# yy_led_display.net
KiCad netlist of a schematic drawn in Altium Designer
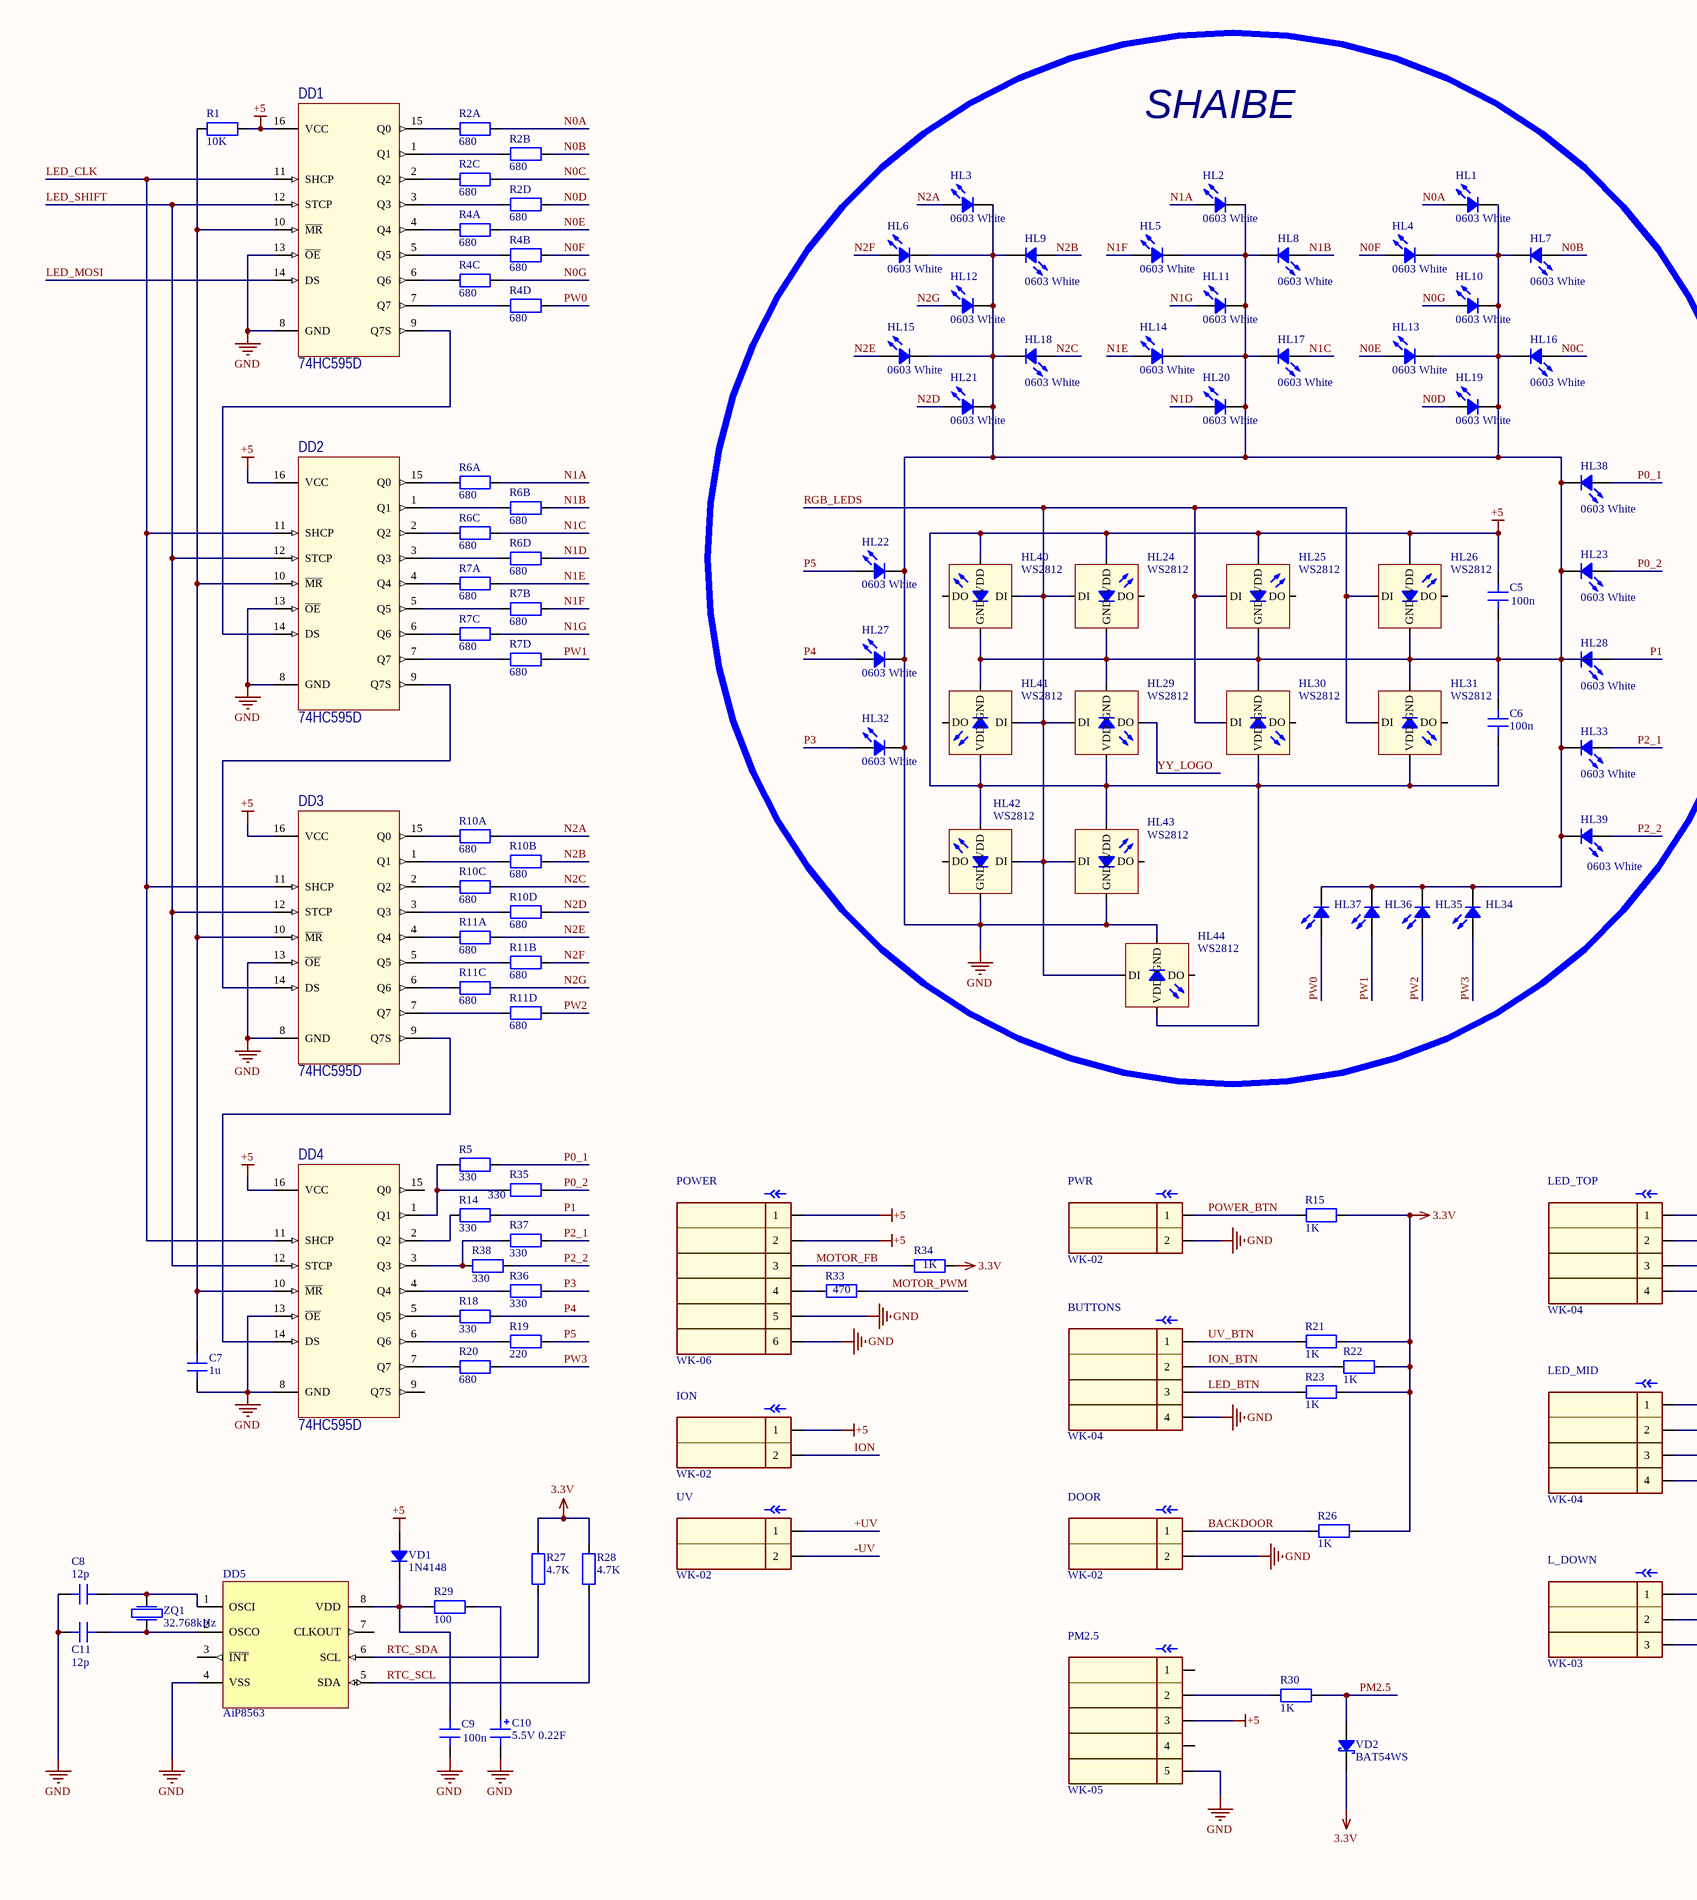
[diagram p0: yy_led_display.SchDoc, left]
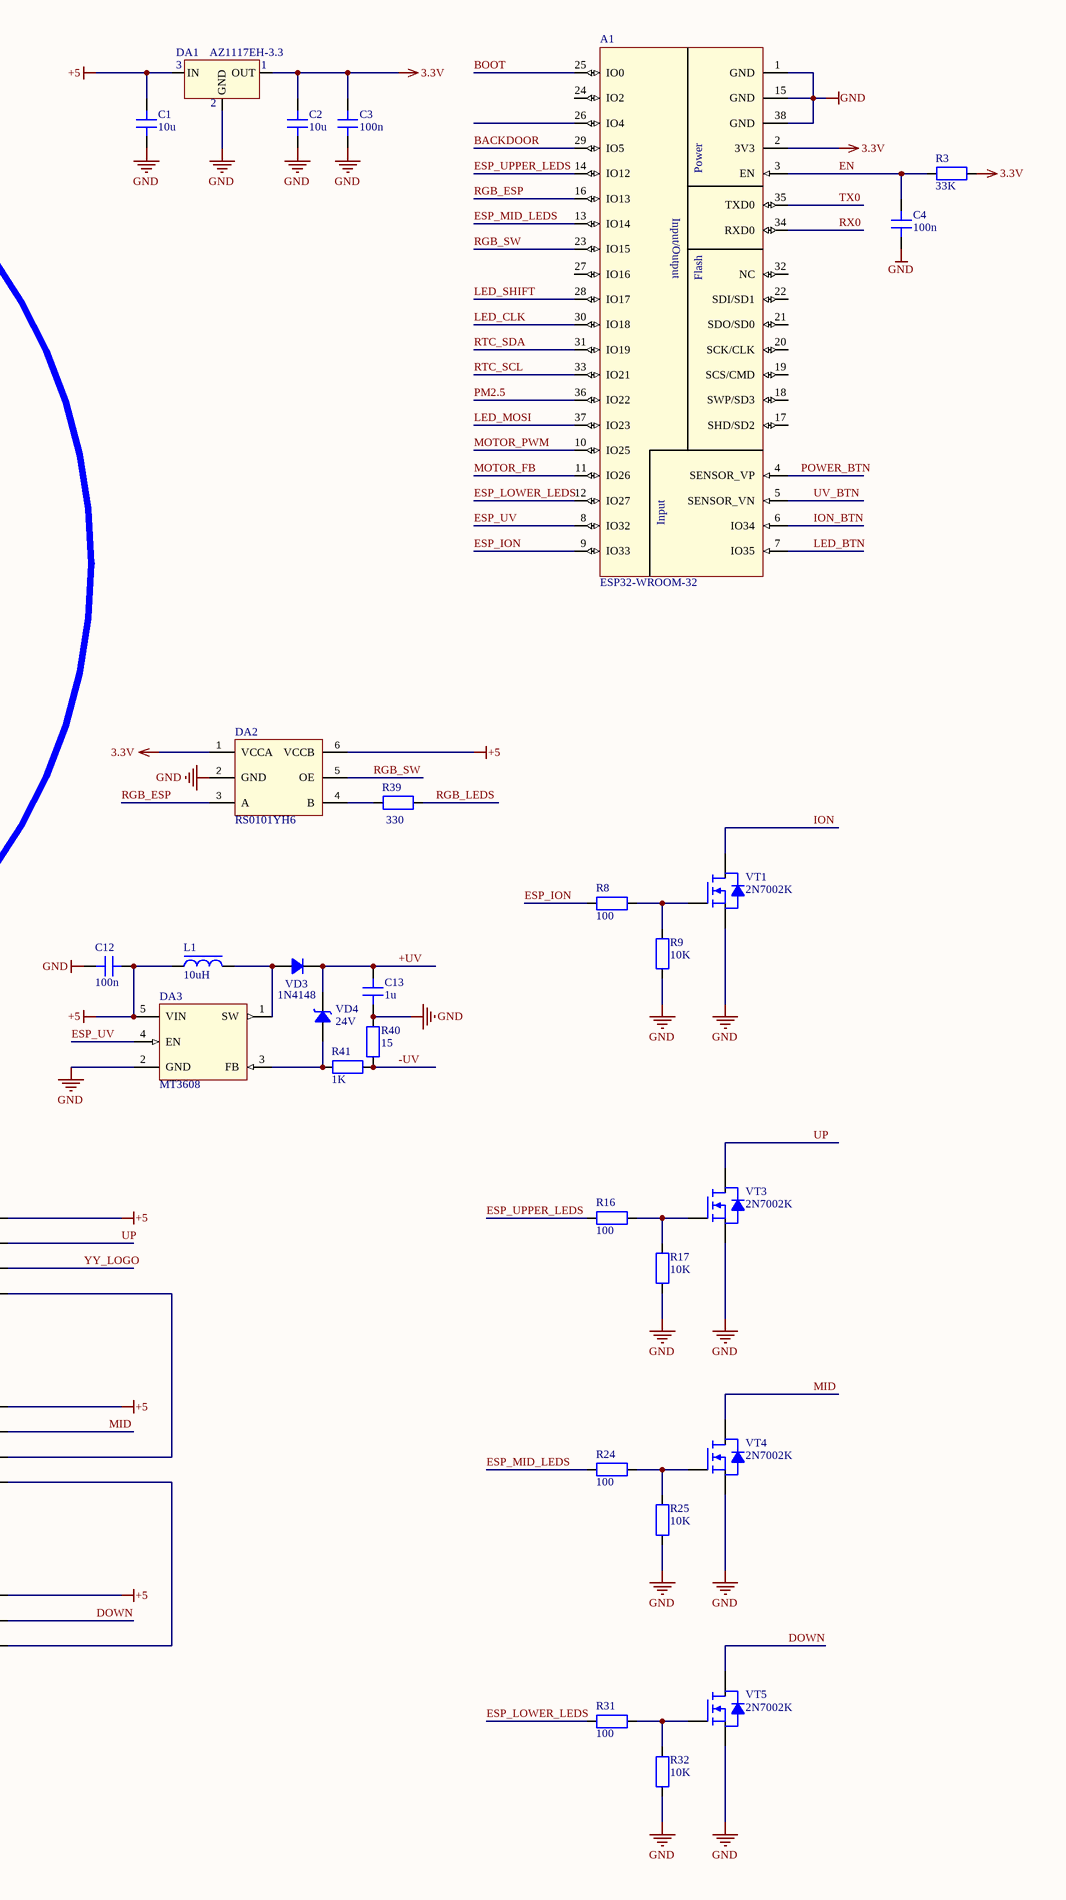
[diagram p1: yy_led_display.SchDoc, right]

(export (version "E")
  (design (tool "Eeschema 10.0.6"))
  (components
    (comp (ref "A1")
      (value "ESP32-WROOM-32")
      (footprint "ESP-WROOM-32")
      (fields (field (name "MANUFACTURER") "Espressif Systems"))
      (libsource (lib "IZTT_Library") (part "ESP32-WROOM-32"))
    )
    (comp (ref "BUTTONS")
      (value "WK-04")
      (footprint "WK-04")
      (description "Through-hole type shrouded header, XH Series, 2.5mm")
      (libsource (lib "IZTT_Library") (part "MALE_4PIN"))
    )
    (comp (ref "C1")
      (value "10u")
      (footprint "C0805")
      (description "Cap Ceramic, 0805, ±10%, 50V, X7R (X5R), -55 +125C (-55 +85C)")
      (libsource (lib "IZTT_Library") (part "Capacitor"))
    )
    (comp (ref "C2")
      (value "10u")
      (footprint "C0805")
      (description "Cap Ceramic, 0805, ±10%, 50V, X7R (X5R), -55 +125C (-55 +85C)")
      (libsource (lib "IZTT_Library") (part "Capacitor"))
    )
    (comp (ref "C3")
      (value "100n")
      (footprint "C0603")
      (description "Cap Ceramic, 0603, ±10%, 50V, X7R (X5R), -55 +125C (-55 +85C)")
      (libsource (lib "IZTT_Library") (part "Capacitor"))
    )
    (comp (ref "C4")
      (value "100n")
      (footprint "C0603")
      (description "Cap Ceramic, 0603, ±10%, 50V, X7R (X5R), -55 +125C (-55 +85C)")
      (libsource (lib "IZTT_Library") (part "Capacitor"))
    )
    (comp (ref "C5")
      (value "100n")
      (footprint "C0603")
      (description "Cap Ceramic, 0603, ±10%, 50V, X7R (X5R), -55 +125C (-55 +85C)")
      (libsource (lib "IZTT_Library") (part "Capacitor"))
    )
    (comp (ref "C6")
      (value "100n")
      (footprint "C0603")
      (description "Cap Ceramic, 0603, ±10%, 50V, X7R (X5R), -55 +125C (-55 +85C)")
      (libsource (lib "IZTT_Library") (part "Capacitor"))
    )
    (comp (ref "C7")
      (value "1u")
      (footprint "C0603")
      (description "Cap Ceramic, 0603, ±10%, 50V, X7R (X5R), -55 +125C (-55 +85C)")
      (libsource (lib "IZTT_Library") (part "Capacitor"))
    )
    (comp (ref "C8")
      (value "12p")
      (footprint "C0603")
      (description "Cap Ceramic, 0603, 5%, 50V, NPO (C0G), -55 +125C")
      (libsource (lib "IZTT_Library") (part "Capacitor"))
    )
    (comp (ref "C9")
      (value "100n")
      (footprint "C0603")
      (description "Cap Ceramic, 0603, ±10%, 50V, X7R (X5R), -55 +125C (-55 +85C)")
      (libsource (lib "IZTT_Library") (part "Capacitor"))
    )
    (comp (ref "C10")
      (value "5.5V 0.22F")
      (footprint "1207H")
      (description "Ionistor 5.5V 0.22F")
      (fields (field (name "MANUFACTURER") "WTSCAP (Wenting)"))
      (libsource (lib "IZTT_Library") (part "Capacitor_polarised"))
    )
    (comp (ref "C11")
      (value "12p")
      (footprint "C0603")
      (description "Cap Ceramic, 0603, 5%, 50V, NPO (C0G), -55 +125C")
      (libsource (lib "IZTT_Library") (part "Capacitor"))
    )
    (comp (ref "C12")
      (value "100n")
      (footprint "C0603")
      (description "Cap Ceramic, 0603, ±10%, 50V, X7R (X5R), -55 +125C (-55 +85C)")
      (libsource (lib "IZTT_Library") (part "Capacitor"))
    )
    (comp (ref "C13")
      (value "1u")
      (footprint "C0603")
      (description "Cap Ceramic, 0603, ±10%, 50V, X7R (X5R), -55 +125C (-55 +85C)")
      (libsource (lib "IZTT_Library") (part "Capacitor"))
    )
    (comp (ref "DA1")
      (value "AZ1117EH-3.3")
      (footprint "SOT-223")
      (description "IC, Vreg, LDO, For Low ESR MLCC Cout, SOT223")
      (libsource (lib "IZTT_Library") (part "LDO_1117"))
    )
    (comp (ref "DA2")
      (value "RS0101YH6")
      (footprint "SOT-23-6")
      (description "Level Translators, Shifters RoHS")
      (fields (field (name "MANUFACTURER") "Jiangsu RUNIC Tech"))
      (libsource (lib "IZTT_Library") (part "RS0101YH6"))
    )
    (comp (ref "DA3")
      (value "MT3608")
      (footprint "SOT-23-6")
      (description "High Efficiency 1.2MHz 2A Step Up Converter")
      (fields (field (name "MANUFACTURER") "XI'AN Aerosemi Tech"))
      (libsource (lib "IZTT_Library") (part "MT3608"))
    )
    (comp (ref "DD1")
      (value "74HC595D")
      (footprint "SO-16")
      (description "Shift Register Serial to parallel, serial SOIC-16_150mil")
      (fields (field (name "MANUFACTURER") "Shenzhen Fuman Elec"))
      (libsource (lib "IZTT_Library") (part "74HC595D"))
    )
    (comp (ref "DD2")
      (value "74HC595D")
      (footprint "SO-16")
      (description "Shift Register Serial to parallel, serial SOIC-16_150mil")
      (fields (field (name "MANUFACTURER") "Shenzhen Fuman Elec"))
      (libsource (lib "IZTT_Library") (part "74HC595D"))
    )
    (comp (ref "DD3")
      (value "74HC595D")
      (footprint "SO-16")
      (description "Shift Register Serial to parallel, serial SOIC-16_150mil")
      (fields (field (name "MANUFACTURER") "Shenzhen Fuman Elec"))
      (libsource (lib "IZTT_Library") (part "74HC595D"))
    )
    (comp (ref "DD4")
      (value "74HC595D")
      (footprint "SO-16")
      (description "Shift Register Serial to parallel, serial SOIC-16_150mil")
      (fields (field (name "MANUFACTURER") "Shenzhen Fuman Elec"))
      (libsource (lib "IZTT_Library") (part "74HC595D"))
    )
    (comp (ref "DD5")
      (value "AiP8563")
      (footprint "SO-8")
      (description "SOP-8 Real-time Clocks RoHS")
      (fields (field (name "MANUFACTURER") "Wuxi I-core Elec"))
      (libsource (lib "IZTT_Library") (part "AiP8563"))
    )
    (comp (ref "DOOR")
      (value "WK-02")
      (footprint "WK-02")
      (description "Through-hole type shrouded header, XH Series, 2.5mm")
      (libsource (lib "IZTT_Library") (part "MALE_2PIN"))
    )
    (comp (ref "HL1")
      (value "0603 White")
      (footprint "LED0603Y")
      (description "LED, SMD 0603, 20mA, White 6000K~7000K")
      (fields (field (name "MANUFACTURER") "HONGLITRONIC(Hongli Zhihui (HONGLITRONIC))"))
      (libsource (lib "IZTT_Library") (part "LED"))
    )
    (comp (ref "HL2")
      (value "0603 White")
      (footprint "LED0603Y")
      (description "LED, SMD 0603, 20mA, White 6000K~7000K")
      (fields (field (name "MANUFACTURER") "HONGLITRONIC(Hongli Zhihui (HONGLITRONIC))"))
      (libsource (lib "IZTT_Library") (part "LED"))
    )
    (comp (ref "HL3")
      (value "0603 White")
      (footprint "LED0603Y")
      (description "LED, SMD 0603, 20mA, White 6000K~7000K")
      (fields (field (name "MANUFACTURER") "HONGLITRONIC(Hongli Zhihui (HONGLITRONIC))"))
      (libsource (lib "IZTT_Library") (part "LED"))
    )
    (comp (ref "HL4")
      (value "0603 White")
      (footprint "LED0603Y")
      (description "LED, SMD 0603, 20mA, White 6000K~7000K")
      (fields (field (name "MANUFACTURER") "HONGLITRONIC(Hongli Zhihui (HONGLITRONIC))"))
      (libsource (lib "IZTT_Library") (part "LED"))
    )
    (comp (ref "HL5")
      (value "0603 White")
      (footprint "LED0603Y")
      (description "LED, SMD 0603, 20mA, White 6000K~7000K")
      (fields (field (name "MANUFACTURER") "HONGLITRONIC(Hongli Zhihui (HONGLITRONIC))"))
      (libsource (lib "IZTT_Library") (part "LED"))
    )
    (comp (ref "HL6")
      (value "0603 White")
      (footprint "LED0603Y")
      (description "LED, SMD 0603, 20mA, White 6000K~7000K")
      (fields (field (name "MANUFACTURER") "HONGLITRONIC(Hongli Zhihui (HONGLITRONIC))"))
      (libsource (lib "IZTT_Library") (part "LED"))
    )
    (comp (ref "HL7")
      (value "0603 White")
      (footprint "LED0603Y")
      (description "LED, SMD 0603, 20mA, White 6000K~7000K")
      (fields (field (name "MANUFACTURER") "HONGLITRONIC(Hongli Zhihui (HONGLITRONIC))"))
      (libsource (lib "IZTT_Library") (part "LED"))
    )
    (comp (ref "HL8")
      (value "0603 White")
      (footprint "LED0603Y")
      (description "LED, SMD 0603, 20mA, White 6000K~7000K")
      (fields (field (name "MANUFACTURER") "HONGLITRONIC(Hongli Zhihui (HONGLITRONIC))"))
      (libsource (lib "IZTT_Library") (part "LED"))
    )
    (comp (ref "HL9")
      (value "0603 White")
      (footprint "LED0603Y")
      (description "LED, SMD 0603, 20mA, White 6000K~7000K")
      (fields (field (name "MANUFACTURER") "HONGLITRONIC(Hongli Zhihui (HONGLITRONIC))"))
      (libsource (lib "IZTT_Library") (part "LED"))
    )
    (comp (ref "HL10")
      (value "0603 White")
      (footprint "LED0603Y")
      (description "LED, SMD 0603, 20mA, White 6000K~7000K")
      (fields (field (name "MANUFACTURER") "HONGLITRONIC(Hongli Zhihui (HONGLITRONIC))"))
      (libsource (lib "IZTT_Library") (part "LED"))
    )
    (comp (ref "HL11")
      (value "0603 White")
      (footprint "LED0603Y")
      (description "LED, SMD 0603, 20mA, White 6000K~7000K")
      (fields (field (name "MANUFACTURER") "HONGLITRONIC(Hongli Zhihui (HONGLITRONIC))"))
      (libsource (lib "IZTT_Library") (part "LED"))
    )
    (comp (ref "HL12")
      (value "0603 White")
      (footprint "LED0603Y")
      (description "LED, SMD 0603, 20mA, White 6000K~7000K")
      (fields (field (name "MANUFACTURER") "HONGLITRONIC(Hongli Zhihui (HONGLITRONIC))"))
      (libsource (lib "IZTT_Library") (part "LED"))
    )
    (comp (ref "HL13")
      (value "0603 White")
      (footprint "LED0603Y")
      (description "LED, SMD 0603, 20mA, White 6000K~7000K")
      (fields (field (name "MANUFACTURER") "HONGLITRONIC(Hongli Zhihui (HONGLITRONIC))"))
      (libsource (lib "IZTT_Library") (part "LED"))
    )
    (comp (ref "HL14")
      (value "0603 White")
      (footprint "LED0603Y")
      (description "LED, SMD 0603, 20mA, White 6000K~7000K")
      (fields (field (name "MANUFACTURER") "HONGLITRONIC(Hongli Zhihui (HONGLITRONIC))"))
      (libsource (lib "IZTT_Library") (part "LED"))
    )
    (comp (ref "HL15")
      (value "0603 White")
      (footprint "LED0603Y")
      (description "LED, SMD 0603, 20mA, White 6000K~7000K")
      (fields (field (name "MANUFACTURER") "HONGLITRONIC(Hongli Zhihui (HONGLITRONIC))"))
      (libsource (lib "IZTT_Library") (part "LED"))
    )
    (comp (ref "HL16")
      (value "0603 White")
      (footprint "LED0603Y")
      (description "LED, SMD 0603, 20mA, White 6000K~7000K")
      (fields (field (name "MANUFACTURER") "HONGLITRONIC(Hongli Zhihui (HONGLITRONIC))"))
      (libsource (lib "IZTT_Library") (part "LED"))
    )
    (comp (ref "HL17")
      (value "0603 White")
      (footprint "LED0603Y")
      (description "LED, SMD 0603, 20mA, White 6000K~7000K")
      (fields (field (name "MANUFACTURER") "HONGLITRONIC(Hongli Zhihui (HONGLITRONIC))"))
      (libsource (lib "IZTT_Library") (part "LED"))
    )
    (comp (ref "HL18")
      (value "0603 White")
      (footprint "LED0603Y")
      (description "LED, SMD 0603, 20mA, White 6000K~7000K")
      (fields (field (name "MANUFACTURER") "HONGLITRONIC(Hongli Zhihui (HONGLITRONIC))"))
      (libsource (lib "IZTT_Library") (part "LED"))
    )
    (comp (ref "HL19")
      (value "0603 White")
      (footprint "LED0603Y")
      (description "LED, SMD 0603, 20mA, White 6000K~7000K")
      (fields (field (name "MANUFACTURER") "HONGLITRONIC(Hongli Zhihui (HONGLITRONIC))"))
      (libsource (lib "IZTT_Library") (part "LED"))
    )
    (comp (ref "HL20")
      (value "0603 White")
      (footprint "LED0603Y")
      (description "LED, SMD 0603, 20mA, White 6000K~7000K")
      (fields (field (name "MANUFACTURER") "HONGLITRONIC(Hongli Zhihui (HONGLITRONIC))"))
      (libsource (lib "IZTT_Library") (part "LED"))
    )
    (comp (ref "HL21")
      (value "0603 White")
      (footprint "LED0603Y")
      (description "LED, SMD 0603, 20mA, White 6000K~7000K")
      (fields (field (name "MANUFACTURER") "HONGLITRONIC(Hongli Zhihui (HONGLITRONIC))"))
      (libsource (lib "IZTT_Library") (part "LED"))
    )
    (comp (ref "HL22")
      (value "0603 White")
      (footprint "LED0603Y")
      (description "LED, SMD 0603, 20mA, White 6000K~7000K")
      (fields (field (name "MANUFACTURER") "HONGLITRONIC(Hongli Zhihui (HONGLITRONIC))"))
      (libsource (lib "IZTT_Library") (part "LED"))
    )
    (comp (ref "HL23")
      (value "0603 White")
      (footprint "LED0603Y")
      (description "LED, SMD 0603, 20mA, White 6000K~7000K")
      (fields (field (name "MANUFACTURER") "HONGLITRONIC(Hongli Zhihui (HONGLITRONIC))"))
      (libsource (lib "IZTT_Library") (part "LED"))
    )
    (comp (ref "HL24")
      (value "WS2812")
      (footprint "WS2812C-2020")
      (description "Intelligent control LED, 2.0x2.0mm")
      (fields (field (name "MANUFACTURER") "Worldsemi"))
      (libsource (lib "IZTT_Library") (part "WS2812C-2020"))
    )
    (comp (ref "HL25")
      (value "WS2812")
      (footprint "WS2812C-2020")
      (description "Intelligent control LED, 2.0x2.0mm")
      (fields (field (name "MANUFACTURER") "Worldsemi"))
      (libsource (lib "IZTT_Library") (part "WS2812C-2020"))
    )
    (comp (ref "HL26")
      (value "WS2812")
      (footprint "WS2812C-2020")
      (description "Intelligent control LED, 2.0x2.0mm")
      (fields (field (name "MANUFACTURER") "Worldsemi"))
      (libsource (lib "IZTT_Library") (part "WS2812C-2020"))
    )
    (comp (ref "HL27")
      (value "0603 White")
      (footprint "LED0603Y")
      (description "LED, SMD 0603, 20mA, White 6000K~7000K")
      (fields (field (name "MANUFACTURER") "HONGLITRONIC(Hongli Zhihui (HONGLITRONIC))"))
      (libsource (lib "IZTT_Library") (part "LED"))
    )
    (comp (ref "HL28")
      (value "0603 White")
      (footprint "LED0603Y")
      (description "LED, SMD 0603, 20mA, White 6000K~7000K")
      (fields (field (name "MANUFACTURER") "HONGLITRONIC(Hongli Zhihui (HONGLITRONIC))"))
      (libsource (lib "IZTT_Library") (part "LED"))
    )
    (comp (ref "HL29")
      (value "WS2812")
      (footprint "WS2812C-2020")
      (description "Intelligent control LED, 2.0x2.0mm")
      (fields (field (name "MANUFACTURER") "Worldsemi"))
      (libsource (lib "") (part "WS2812C-2020_3"))
    )
    (comp (ref "HL30")
      (value "WS2812")
      (footprint "WS2812C-2020")
      (description "Intelligent control LED, 2.0x2.0mm")
      (fields (field (name "MANUFACTURER") "Worldsemi"))
      (libsource (lib "") (part "WS2812C-2020_3"))
    )
    (comp (ref "HL31")
      (value "WS2812")
      (footprint "WS2812C-2020")
      (description "Intelligent control LED, 2.0x2.0mm")
      (fields (field (name "MANUFACTURER") "Worldsemi"))
      (libsource (lib "") (part "WS2812C-2020_3"))
    )
    (comp (ref "HL32")
      (value "0603 White")
      (footprint "LED0603Y")
      (description "LED, SMD 0603, 20mA, White 6000K~7000K")
      (fields (field (name "MANUFACTURER") "HONGLITRONIC(Hongli Zhihui (HONGLITRONIC))"))
      (libsource (lib "IZTT_Library") (part "LED"))
    )
    (comp (ref "HL33")
      (value "0603 White")
      (footprint "LED0603Y")
      (description "LED, SMD 0603, 20mA, White 6000K~7000K")
      (fields (field (name "MANUFACTURER") "HONGLITRONIC(Hongli Zhihui (HONGLITRONIC))"))
      (libsource (lib "IZTT_Library") (part "LED"))
    )
    (comp (ref "HL34")
      (value "0603 White")
      (footprint "LED0603Y")
      (description "LED, SMD 0603, 20mA, White 6000K~7000K")
      (fields (field (name "MANUFACTURER") "HONGLITRONIC(Hongli Zhihui (HONGLITRONIC))"))
      (libsource (lib "IZTT_Library") (part "LED"))
    )
    (comp (ref "HL35")
      (value "0603 White")
      (footprint "LED0603Y")
      (description "LED, SMD 0603, 20mA, White 6000K~7000K")
      (fields (field (name "MANUFACTURER") "HONGLITRONIC(Hongli Zhihui (HONGLITRONIC))"))
      (libsource (lib "IZTT_Library") (part "LED"))
    )
    (comp (ref "HL36")
      (value "0603 White")
      (footprint "LED0603Y")
      (description "LED, SMD 0603, 20mA, White 6000K~7000K")
      (fields (field (name "MANUFACTURER") "HONGLITRONIC(Hongli Zhihui (HONGLITRONIC))"))
      (libsource (lib "IZTT_Library") (part "LED"))
    )
    (comp (ref "HL37")
      (value "0603 White")
      (footprint "LED0603Y")
      (description "LED, SMD 0603, 20mA, White 6000K~7000K")
      (fields (field (name "MANUFACTURER") "HONGLITRONIC(Hongli Zhihui (HONGLITRONIC))"))
      (libsource (lib "IZTT_Library") (part "LED"))
    )
    (comp (ref "HL38")
      (value "0603 White")
      (footprint "LED0603Y")
      (description "LED, SMD 0603, 20mA, White 6000K~7000K")
      (fields (field (name "MANUFACTURER") "HONGLITRONIC(Hongli Zhihui (HONGLITRONIC))"))
      (libsource (lib "IZTT_Library") (part "LED"))
    )
    (comp (ref "HL39")
      (value "0603 White")
      (footprint "LED0603Y")
      (description "LED, SMD 0603, 20mA, White 6000K~7000K")
      (fields (field (name "MANUFACTURER") "HONGLITRONIC(Hongli Zhihui (HONGLITRONIC))"))
      (libsource (lib "IZTT_Library") (part "LED"))
    )
    (comp (ref "HL40")
      (value "WS2812")
      (footprint "WS2812C-2020")
      (description "Intelligent control LED, 2.0x2.0mm")
      (fields (field (name "MANUFACTURER") "Worldsemi"))
      (libsource (lib "") (part "WS2812C-2020_1"))
    )
    (comp (ref "HL41")
      (value "WS2812")
      (footprint "WS2812C-2020")
      (description "Intelligent control LED, 2.0x2.0mm")
      (fields (field (name "MANUFACTURER") "Worldsemi"))
      (libsource (lib "") (part "WS2812C-2020_2"))
    )
    (comp (ref "HL42")
      (value "WS2812")
      (footprint "WS2812C-2020")
      (description "Intelligent control LED, 2.0x2.0mm")
      (fields (field (name "MANUFACTURER") "Worldsemi"))
      (libsource (lib "") (part "WS2812C-2020_1"))
    )
    (comp (ref "HL43")
      (value "WS2812")
      (footprint "WS2812C-2020")
      (description "Intelligent control LED, 2.0x2.0mm")
      (fields (field (name "MANUFACTURER") "Worldsemi"))
      (libsource (lib "IZTT_Library") (part "WS2812C-2020"))
    )
    (comp (ref "HL44")
      (value "WS2812")
      (footprint "WS2812C-2020")
      (description "Intelligent control LED, 2.0x2.0mm")
      (fields (field (name "MANUFACTURER") "Worldsemi"))
      (libsource (lib "") (part "WS2812C-2020_3"))
    )
    (comp (ref "ION")
      (value "WK-02")
      (footprint "WK-02")
      (description "Through-hole type shrouded header, XH Series, 2.5mm")
      (libsource (lib "IZTT_Library") (part "MALE_2PIN"))
    )
    (comp (ref "L1")
      (value "10uH")
      (footprint "SCD0302_OR_L1206")
      (description "SMD Power Inductors, 10uH ±20% 350mA 350mΩ SMD,3.5x3x2.1mm")
      (fields (field (name "MANUFACTURER") "Sunltech Tech"))
      (libsource (lib "IZTT_Library") (part "Drossel"))
    )
    (comp (ref "LED_MID")
      (value "WK-04")
      (footprint "WK-04")
      (description "Through-hole type shrouded header, XH Series, 2.5mm")
      (libsource (lib "IZTT_Library") (part "MALE_4PIN"))
    )
    (comp (ref "LED_TOP")
      (value "WK-04")
      (footprint "WK-04")
      (description "Through-hole type shrouded header, XH Series, 2.5mm")
      (libsource (lib "IZTT_Library") (part "MALE_4PIN"))
    )
    (comp (ref "L_DOWN")
      (value "WK-03")
      (footprint "WK-03")
      (description "Through-hole type shrouded header, XH Series, 2.5mm")
      (libsource (lib "IZTT_Library") (part "MALE_3PIN"))
    )
    (comp (ref "PM2.5")
      (value "WK-05")
      (footprint "WK-05")
      (description "Through-hole type shrouded header, XH Series, 2.5mm")
      (libsource (lib "IZTT_Library") (part "MALE_5PIN"))
    )
    (comp (ref "POWER")
      (value "WK-06")
      (footprint "WK-06")
      (description "Through-hole type shrouded header, XH Series, 2.5mm")
      (libsource (lib "IZTT_Library") (part "MALE_6PIN"))
    )
    (comp (ref "PWR")
      (value "WK-02")
      (footprint "WK-02")
      (description "Through-hole type shrouded header, XH Series, 2.5mm")
      (libsource (lib "IZTT_Library") (part "MALE_2PIN"))
    )
    (comp (ref "R1")
      (value "10K")
      (footprint "R0603")
      (description "Res, 0603, 1%, 1/10W")
      (fields (field (name "MANUFACTURER") "FH(Guangdong Fenghua Advanced Tech)"))
      (libsource (lib "IZTT_Library") (part "Resistor"))
    )
    (comp (ref "R2")
      (value "680")
      (footprint "RESA_4x0402")
      (description "680 ±5% 4 1/16W ±200ppm/℃ 0402_x4 Resistor Networks & Arrays RoHS")
      (fields (field (name "MANUFACTURER") "RALEC"))
      (libsource (lib "IZTT_Library") (part "Resistor_array_4"))
    )
    (comp (ref "R3")
      (value "33K")
      (footprint "R0603")
      (description "Res, 0603, 1%, 1/10W")
      (fields (field (name "MANUFACTURER") "UNI-ROYAL(Uniroyal Elec)"))
      (libsource (lib "IZTT_Library") (part "Resistor"))
    )
    (comp (ref "R4")
      (value "680")
      (footprint "RESA_4x0402")
      (description "680 ±5% 4 1/16W ±200ppm/℃ 0402_x4 Resistor Networks & Arrays RoHS")
      (fields (field (name "MANUFACTURER") "RALEC"))
      (libsource (lib "IZTT_Library") (part "Resistor_array_4"))
    )
    (comp (ref "R5")
      (value "330")
      (footprint "R0603")
      (description "Res, 0603, 1%, 1/10W")
      (fields (field (name "MANUFACTURER") "Walsin Tech Corp"))
      (libsource (lib "IZTT_Library") (part "Resistor"))
    )
    (comp (ref "R6")
      (value "680")
      (footprint "RESA_4x0402")
      (description "680 ±5% 4 1/16W ±200ppm/℃ 0402_x4 Resistor Networks & Arrays RoHS")
      (fields (field (name "MANUFACTURER") "RALEC"))
      (libsource (lib "IZTT_Library") (part "Resistor_array_4"))
    )
    (comp (ref "R7")
      (value "680")
      (footprint "RESA_4x0402")
      (description "680 ±5% 4 1/16W ±200ppm/℃ 0402_x4 Resistor Networks & Arrays RoHS")
      (fields (field (name "MANUFACTURER") "RALEC"))
      (libsource (lib "IZTT_Library") (part "Resistor_array_4"))
    )
    (comp (ref "R8")
      (value "100")
      (footprint "R0603")
      (description "Res, 0603, 1%, 1/10W")
      (fields (field (name "MANUFACTURER") "UNI-ROYAL(Uniroyal Elec)"))
      (libsource (lib "IZTT_Library") (part "Resistor"))
    )
    (comp (ref "R9")
      (value "10K")
      (footprint "R0603")
      (description "Res, 0603, 1%, 1/10W")
      (fields (field (name "MANUFACTURER") "FH(Guangdong Fenghua Advanced Tech)"))
      (libsource (lib "IZTT_Library") (part "Resistor"))
    )
    (comp (ref "R10")
      (value "680")
      (footprint "RESA_4x0402")
      (description "680 ±5% 4 1/16W ±200ppm/℃ 0402_x4 Resistor Networks & Arrays RoHS")
      (fields (field (name "MANUFACTURER") "RALEC"))
      (libsource (lib "IZTT_Library") (part "Resistor_array_4"))
    )
    (comp (ref "R11")
      (value "680")
      (footprint "RESA_4x0402")
      (description "680 ±5% 4 1/16W ±200ppm/℃ 0402_x4 Resistor Networks & Arrays RoHS")
      (fields (field (name "MANUFACTURER") "RALEC"))
      (libsource (lib "IZTT_Library") (part "Resistor_array_4"))
    )
    (comp (ref "R14")
      (value "330")
      (footprint "R0603")
      (description "Res, 0603, 1%, 1/10W")
      (fields (field (name "MANUFACTURER") "Walsin Tech Corp"))
      (libsource (lib "IZTT_Library") (part "Resistor"))
    )
    (comp (ref "R15")
      (value "1K")
      (footprint "R0603")
      (description "Res, 0603, 1%, 1/10W")
      (fields (field (name "MANUFACTURER") "FH(Guangdong Fenghua Advanced Tech)"))
      (libsource (lib "IZTT_Library") (part "Resistor"))
    )
    (comp (ref "R16")
      (value "100")
      (footprint "R0603")
      (description "Res, 0603, 1%, 1/10W")
      (fields (field (name "MANUFACTURER") "UNI-ROYAL(Uniroyal Elec)"))
      (libsource (lib "IZTT_Library") (part "Resistor"))
    )
    (comp (ref "R17")
      (value "10K")
      (footprint "R0603")
      (description "Res, 0603, 1%, 1/10W")
      (fields (field (name "MANUFACTURER") "FH(Guangdong Fenghua Advanced Tech)"))
      (libsource (lib "IZTT_Library") (part "Resistor"))
    )
    (comp (ref "R18")
      (value "330")
      (footprint "R0603")
      (description "Res, 0603, 1%, 1/10W")
      (fields (field (name "MANUFACTURER") "Walsin Tech Corp"))
      (libsource (lib "IZTT_Library") (part "Resistor"))
    )
    (comp (ref "R19")
      (value "220")
      (footprint "R0603")
      (description "Res, 0603, 1%, 1/10W")
      (fields (field (name "MANUFACTURER") "UNI-ROYAL(Uniroyal Elec)"))
      (libsource (lib "IZTT_Library") (part "Resistor"))
    )
    (comp (ref "R20")
      (value "680")
      (footprint "R0603")
      (description "Res, 0603, 1%, 1/10W")
      (fields (field (name "MANUFACTURER") "UNI-ROYAL(Uniroyal Elec)"))
      (libsource (lib "IZTT_Library") (part "Resistor"))
    )
    (comp (ref "R21")
      (value "1K")
      (footprint "R0603")
      (description "Res, 0603, 1%, 1/10W")
      (fields (field (name "MANUFACTURER") "FH(Guangdong Fenghua Advanced Tech)"))
      (libsource (lib "IZTT_Library") (part "Resistor"))
    )
    (comp (ref "R22")
      (value "1K")
      (footprint "R0603")
      (description "Res, 0603, 1%, 1/10W")
      (fields (field (name "MANUFACTURER") "FH(Guangdong Fenghua Advanced Tech)"))
      (libsource (lib "IZTT_Library") (part "Resistor"))
    )
    (comp (ref "R23")
      (value "1K")
      (footprint "R0603")
      (description "Res, 0603, 1%, 1/10W")
      (fields (field (name "MANUFACTURER") "FH(Guangdong Fenghua Advanced Tech)"))
      (libsource (lib "IZTT_Library") (part "Resistor"))
    )
    (comp (ref "R24")
      (value "100")
      (footprint "R0603")
      (description "Res, 0603, 1%, 1/10W")
      (fields (field (name "MANUFACTURER") "UNI-ROYAL(Uniroyal Elec)"))
      (libsource (lib "IZTT_Library") (part "Resistor"))
    )
    (comp (ref "R25")
      (value "10K")
      (footprint "R0603")
      (description "Res, 0603, 1%, 1/10W")
      (fields (field (name "MANUFACTURER") "FH(Guangdong Fenghua Advanced Tech)"))
      (libsource (lib "IZTT_Library") (part "Resistor"))
    )
    (comp (ref "R26")
      (value "1K")
      (footprint "R0603")
      (description "Res, 0603, 1%, 1/10W")
      (fields (field (name "MANUFACTURER") "FH(Guangdong Fenghua Advanced Tech)"))
      (libsource (lib "IZTT_Library") (part "Resistor"))
    )
    (comp (ref "R27")
      (value "4.7K")
      (footprint "R0603")
      (description "Res, 0603, 1%, 1/10W")
      (fields (field (name "MANUFACTURER") "UNI-ROYAL(Uniroyal Elec)"))
      (libsource (lib "IZTT_Library") (part "Resistor"))
    )
    (comp (ref "R28")
      (value "4.7K")
      (footprint "R0603")
      (description "Res, 0603, 1%, 1/10W")
      (fields (field (name "MANUFACTURER") "UNI-ROYAL(Uniroyal Elec)"))
      (libsource (lib "IZTT_Library") (part "Resistor"))
    )
    (comp (ref "R29")
      (value "100")
      (footprint "R0603")
      (description "Res, 0603, 1%, 1/10W")
      (fields (field (name "MANUFACTURER") "UNI-ROYAL(Uniroyal Elec)"))
      (libsource (lib "IZTT_Library") (part "Resistor"))
    )
    (comp (ref "R30")
      (value "1K")
      (footprint "R0603")
      (description "Res, 0603, 1%, 1/10W")
      (fields (field (name "MANUFACTURER") "FH(Guangdong Fenghua Advanced Tech)"))
      (libsource (lib "IZTT_Library") (part "Resistor"))
    )
    (comp (ref "R31")
      (value "100")
      (footprint "R0603")
      (description "Res, 0603, 1%, 1/10W")
      (fields (field (name "MANUFACTURER") "UNI-ROYAL(Uniroyal Elec)"))
      (libsource (lib "IZTT_Library") (part "Resistor"))
    )
    (comp (ref "R32")
      (value "10K")
      (footprint "R0603")
      (description "Res, 0603, 1%, 1/10W")
      (fields (field (name "MANUFACTURER") "FH(Guangdong Fenghua Advanced Tech)"))
      (libsource (lib "IZTT_Library") (part "Resistor"))
    )
    (comp (ref "R33")
      (value "470")
      (footprint "R0603")
      (description "Res, 0603, 1%, 1/10W")
      (fields (field (name "MANUFACTURER") "FH(Guangdong Fenghua Advanced Tech)"))
      (libsource (lib "IZTT_Library") (part "Resistor"))
    )
    (comp (ref "R34")
      (value "1K")
      (footprint "R0603")
      (description "Res, 0603, 1%, 1/10W")
      (fields (field (name "MANUFACTURER") "FH(Guangdong Fenghua Advanced Tech)"))
      (libsource (lib "IZTT_Library") (part "Resistor"))
    )
    (comp (ref "R35")
      (value "330")
      (footprint "R0603")
      (description "Res, 0603, 1%, 1/10W")
      (fields (field (name "MANUFACTURER") "Walsin Tech Corp"))
      (libsource (lib "IZTT_Library") (part "Resistor"))
    )
    (comp (ref "R36")
      (value "330")
      (footprint "R0603")
      (description "Res, 0603, 1%, 1/10W")
      (fields (field (name "MANUFACTURER") "Walsin Tech Corp"))
      (libsource (lib "IZTT_Library") (part "Resistor"))
    )
    (comp (ref "R37")
      (value "330")
      (footprint "R0603")
      (description "Res, 0603, 1%, 1/10W")
      (fields (field (name "MANUFACTURER") "Walsin Tech Corp"))
      (libsource (lib "IZTT_Library") (part "Resistor"))
    )
    (comp (ref "R38")
      (value "330")
      (footprint "R0603")
      (description "Res, 0603, 1%, 1/10W")
      (fields (field (name "MANUFACTURER") "Walsin Tech Corp"))
      (libsource (lib "IZTT_Library") (part "Resistor"))
    )
    (comp (ref "R39")
      (value "330")
      (footprint "R0603")
      (description "Res, 0603, 1%, 1/10W")
      (fields (field (name "MANUFACTURER") "Walsin Tech Corp"))
      (libsource (lib "IZTT_Library") (part "Resistor"))
    )
    (comp (ref "R40")
      (value "15")
      (footprint "R0603")
      (description "Res, 0603, 1%, 1/10W")
      (fields (field (name "MANUFACTURER") "UNI-ROYAL(Uniroyal Elec)"))
      (libsource (lib "IZTT_Library") (part "Resistor"))
    )
    (comp (ref "R41")
      (value "1K")
      (footprint "R0603")
      (description "Res, 0603, 1%, 1/10W")
      (fields (field (name "MANUFACTURER") "FH(Guangdong Fenghua Advanced Tech)"))
      (libsource (lib "IZTT_Library") (part "Resistor"))
    )
    (comp (ref "UV")
      (value "WK-02")
      (footprint "WK-02")
      (description "Through-hole type shrouded header, XH Series, 2.5mm")
      (libsource (lib "IZTT_Library") (part "MALE_2PIN"))
    )
    (comp (ref "VD1")
      (value "1N4148")
      (footprint "SOD-323_DIODE")
      (description "Small Signal Fast Switching Diode, 150mA, 75V")
      (libsource (lib "IZTT_Library") (part "Diode"))
    )
    (comp (ref "VD2")
      (value "BAT54WS")
      (footprint "SOD-323_DIODE")
      (description "30V 100mA 1V @ 100mA SOD-323 Schottky Barrier Diodes (SBD) RoHS")
      (fields (field (name "MANUFACTURER") "LGE"))
      (libsource (lib "IZTT_Library") (part "Shottky"))
    )
    (comp (ref "VD3")
      (value "1N4148")
      (footprint "SOD-323_DIODE")
      (description "Small Signal Fast Switching Diode, 150mA, 75V")
      (libsource (lib "IZTT_Library") (part "Diode"))
    )
    (comp (ref "VD4")
      (value "24V")
      (footprint "MiniMELF_Diode")
      (description "Zener Diode, 24V, 500mW, 0.1uA, LL-34")
      (fields (field (name "MANUFACTURER") "ST(Semtech)"))
      (libsource (lib "IZTT_Library") (part "Zener_TVS"))
    )
    (comp (ref "VT1")
      (value "2N7002K")
      (footprint "SOT-23-3")
      (description "HEXFET Power MOSFET N-CH")
      (libsource (lib "IZTT_Library") (part "N-MOS"))
    )
    (comp (ref "VT3")
      (value "2N7002K")
      (footprint "SOT-23-3")
      (description "HEXFET Power MOSFET N-CH")
      (libsource (lib "IZTT_Library") (part "N-MOS"))
    )
    (comp (ref "VT4")
      (value "2N7002K")
      (footprint "SOT-23-3")
      (description "HEXFET Power MOSFET N-CH")
      (libsource (lib "IZTT_Library") (part "N-MOS"))
    )
    (comp (ref "VT5")
      (value "2N7002K")
      (footprint "SOT-23-3")
      (description "HEXFET Power MOSFET N-CH")
      (libsource (lib "IZTT_Library") (part "N-MOS"))
    )
    (comp (ref "ZQ1")
      (value "32.768kHz")
      (footprint "KX-327NHT")
      (description "Quartz 32.768kHz 12.5pF 20ppm")
      (libsource (lib "IZTT_Library") (part "QUARTZ"))
    )
  )
  (nets
    (net (code "1") (name "+5") (class "Default")
      (node (ref "C1") (pin "2") (pinfunction "2_2") (pintype "passive"))
      (node (ref "C12") (pin "2") (pinfunction "2_2") (pintype "passive"))
      (node (ref "C5") (pin "2") (pinfunction "2_2") (pintype "passive"))
      (node (ref "C6") (pin "1") (pinfunction "1_1") (pintype "passive"))
      (node (ref "DA1") (pin "Z") (pinfunction "IN_Z") (pintype "passive"))
      (node (ref "DA2") (pin "6") (pinfunction "VCCB_6") (pintype "passive"))
      (node (ref "DA3") (pin "5") (pinfunction "VIN_5") (pintype "power_in"))
      (node (ref "DD1") (pin "16") (pinfunction "VCC_16") (pintype "power_in"))
      (node (ref "DD2") (pin "16") (pinfunction "VCC_16") (pintype "power_in"))
      (node (ref "DD3") (pin "16") (pinfunction "VCC_16") (pintype "power_in"))
      (node (ref "DD4") (pin "16") (pinfunction "VCC_16") (pintype "power_in"))
      (node (ref "HL24") (pin "+") (pinfunction "VDD_+") (pintype "passive"))
      (node (ref "HL25") (pin "+") (pinfunction "VDD_+") (pintype "passive"))
      (node (ref "HL26") (pin "+") (pinfunction "VDD_+") (pintype "passive"))
      (node (ref "HL29") (pin "+") (pinfunction "VDD_+") (pintype "passive"))
      (node (ref "HL30") (pin "+") (pinfunction "VDD_+") (pintype "passive"))
      (node (ref "HL31") (pin "+") (pinfunction "VDD_+") (pintype "passive"))
      (node (ref "HL40") (pin "+") (pinfunction "VDD_+") (pintype "passive"))
      (node (ref "HL41") (pin "+") (pinfunction "VDD_+") (pintype "passive"))
      (node (ref "HL42") (pin "+") (pinfunction "VDD_+") (pintype "passive"))
      (node (ref "HL43") (pin "+") (pinfunction "VDD_+") (pintype "passive"))
      (node (ref "HL44") (pin "+") (pinfunction "VDD_+") (pintype "passive"))
      (node (ref "ION") (pin "1") (pinfunction "1_1") (pintype "passive"))
      (node (ref "L1") (pin "1") (pinfunction "1_1") (pintype "passive"))
      (node (ref "LED_MID") (pin "1") (pinfunction "1_1") (pintype "passive"))
      (node (ref "LED_TOP") (pin "1") (pinfunction "1_1") (pintype "passive"))
      (node (ref "L_DOWN") (pin "1") (pinfunction "1_1") (pintype "passive"))
      (node (ref "PM2.5") (pin "3") (pinfunction "3_3") (pintype "passive"))
      (node (ref "POWER") (pin "1") (pinfunction "1_1") (pintype "passive"))
      (node (ref "POWER") (pin "2") (pinfunction "2_2") (pintype "passive"))
      (node (ref "R1") (pin "2") (pinfunction "2_2") (pintype "passive"))
      (node (ref "VD1") (pin "A") (pinfunction "A_A") (pintype "passive"))
    )
    (net (code "2") (name "/+UV") (class "Default")
      (node (ref "C13") (pin "2") (pinfunction "2_2") (pintype "passive"))
      (node (ref "UV") (pin "1") (pinfunction "1_1") (pintype "passive"))
      (node (ref "VD3") (pin "C") (pinfunction "C_C") (pintype "passive"))
      (node (ref "VD4") (pin "C") (pinfunction "C_C") (pintype "passive"))
    )
    (net (code "3") (name "/-UV") (class "Default")
      (node (ref "R40") (pin "2") (pinfunction "2_2") (pintype "passive"))
      (node (ref "R41") (pin "2") (pinfunction "2_2") (pintype "passive"))
      (node (ref "UV") (pin "2") (pinfunction "2_2") (pintype "passive"))
    )
    (net (code "4") (name "/BACKDOOR") (class "Default")
      (node (ref "A1") (pin "29") (pinfunction "IO5_29") (pintype "bidirectional"))
      (node (ref "DOOR") (pin "1") (pinfunction "1_1") (pintype "passive"))
      (node (ref "R26") (pin "1") (pinfunction "1_1") (pintype "passive"))
    )
    (net (code "5") (name "/BOOT") (class "Default")
      (node (ref "A1") (pin "25") (pinfunction "IO0_25") (pintype "bidirectional"))
    )
    (net (code "6") (name "/DOWN") (class "Default")
      (node (ref "L_DOWN") (pin "2") (pinfunction "2_2") (pintype "passive"))
      (node (ref "VT5") (pin "Y") (pinfunction "D_Y") (pintype "passive"))
    )
    (net (code "7") (name "/EN") (class "Default")
      (node (ref "A1") (pin "3") (pinfunction "EN_3") (pintype "input"))
      (node (ref "C4") (pin "2") (pinfunction "2_2") (pintype "passive"))
      (node (ref "R3") (pin "1") (pinfunction "1_1") (pintype "passive"))
    )
    (net (code "8") (name "/ESP_ION") (class "Default")
      (node (ref "A1") (pin "9") (pinfunction "IO33_9") (pintype "bidirectional"))
      (node (ref "R8") (pin "1") (pinfunction "1_1") (pintype "passive"))
    )
    (net (code "9") (name "/ESP_LOWER_LEDS") (class "Default")
      (node (ref "A1") (pin "12") (pinfunction "IO27_12") (pintype "bidirectional"))
      (node (ref "R31") (pin "1") (pinfunction "1_1") (pintype "passive"))
    )
    (net (code "10") (name "/ESP_MID_LEDS") (class "Default")
      (node (ref "A1") (pin "13") (pinfunction "IO14_13") (pintype "bidirectional"))
      (node (ref "R24") (pin "1") (pinfunction "1_1") (pintype "passive"))
    )
    (net (code "11") (name "/ESP_UPPER_LEDS") (class "Default")
      (node (ref "A1") (pin "14") (pinfunction "IO12_14") (pintype "bidirectional"))
      (node (ref "R16") (pin "1") (pinfunction "1_1") (pintype "passive"))
    )
    (net (code "12") (name "/ESP_UV") (class "Default")
      (node (ref "A1") (pin "8") (pinfunction "IO32_8") (pintype "bidirectional"))
      (node (ref "DA3") (pin "4") (pinfunction "EN_4") (pintype "input"))
    )
    (net (code "13") (name "/ION") (class "Default")
      (node (ref "ION") (pin "2") (pinfunction "2_2") (pintype "passive"))
      (node (ref "VT1") (pin "Y") (pinfunction "D_Y") (pintype "passive"))
    )
    (net (code "14") (name "/ION_BTN") (class "Default")
      (node (ref "A1") (pin "6") (pinfunction "IO34_6") (pintype "input"))
      (node (ref "BUTTONS") (pin "2") (pinfunction "2_2") (pintype "passive"))
      (node (ref "R22") (pin "1") (pinfunction "1_1") (pintype "passive"))
    )
    (net (code "15") (name "/LED_BTN") (class "Default")
      (node (ref "A1") (pin "7") (pinfunction "IO35_7") (pintype "input"))
      (node (ref "BUTTONS") (pin "3") (pinfunction "3_3") (pintype "passive"))
      (node (ref "R23") (pin "1") (pinfunction "1_1") (pintype "passive"))
    )
    (net (code "16") (name "/LED_CLK") (class "Default")
      (node (ref "A1") (pin "30") (pinfunction "IO18_30") (pintype "bidirectional"))
      (node (ref "DD1") (pin "11") (pinfunction "SHCP_11") (pintype "input"))
      (node (ref "DD2") (pin "11") (pinfunction "SHCP_11") (pintype "input"))
      (node (ref "DD3") (pin "11") (pinfunction "SHCP_11") (pintype "input"))
      (node (ref "DD4") (pin "11") (pinfunction "SHCP_11") (pintype "input"))
    )
    (net (code "17") (name "/LED_MOSI") (class "Default")
      (node (ref "A1") (pin "37") (pinfunction "IO23_37") (pintype "bidirectional"))
      (node (ref "DD1") (pin "14") (pinfunction "DS_14") (pintype "input"))
    )
    (net (code "18") (name "/LED_SHIFT") (class "Default")
      (node (ref "A1") (pin "28") (pinfunction "IO17_28") (pintype "bidirectional"))
      (node (ref "DD1") (pin "12") (pinfunction "STCP_12") (pintype "input"))
      (node (ref "DD2") (pin "12") (pinfunction "STCP_12") (pintype "input"))
      (node (ref "DD3") (pin "12") (pinfunction "STCP_12") (pintype "input"))
      (node (ref "DD4") (pin "12") (pinfunction "STCP_12") (pintype "input"))
    )
    (net (code "19") (name "/MID") (class "Default")
      (node (ref "LED_MID") (pin "2") (pinfunction "2_2") (pintype "passive"))
      (node (ref "VT4") (pin "Y") (pinfunction "D_Y") (pintype "passive"))
    )
    (net (code "20") (name "/MOTOR_FB") (class "Default")
      (node (ref "A1") (pin "11") (pinfunction "IO26_11") (pintype "bidirectional"))
      (node (ref "POWER") (pin "3") (pinfunction "3_3") (pintype "passive"))
      (node (ref "R34") (pin "1") (pinfunction "1_1") (pintype "passive"))
    )
    (net (code "21") (name "/MOTOR_PWM") (class "Default")
      (node (ref "A1") (pin "10") (pinfunction "IO25_10") (pintype "bidirectional"))
      (node (ref "R33") (pin "2") (pinfunction "2_2") (pintype "passive"))
    )
    (net (code "22") (name "/N0A") (class "Default")
      (node (ref "HL1") (pin "A") (pinfunction "A_A") (pintype "passive"))
      (node (ref "R2") (pin "A2") (pinfunction "A2_A2") (pintype "passive"))
    )
    (net (code "23") (name "/N0B") (class "Default")
      (node (ref "HL7") (pin "A") (pinfunction "A_A") (pintype "passive"))
      (node (ref "R2") (pin "B2") (pinfunction "B2_B2") (pintype "passive"))
    )
    (net (code "24") (name "/N0C") (class "Default")
      (node (ref "HL16") (pin "A") (pinfunction "A_A") (pintype "passive"))
      (node (ref "R2") (pin "C2") (pinfunction "C2_C2") (pintype "passive"))
    )
    (net (code "25") (name "/N0D") (class "Default")
      (node (ref "HL19") (pin "A") (pinfunction "A_A") (pintype "passive"))
      (node (ref "R2") (pin "D2") (pinfunction "D2_D2") (pintype "passive"))
    )
    (net (code "26") (name "/N0E") (class "Default")
      (node (ref "HL13") (pin "A") (pinfunction "A_A") (pintype "passive"))
      (node (ref "R4") (pin "A2") (pinfunction "A2_A2") (pintype "passive"))
    )
    (net (code "27") (name "/N0F") (class "Default")
      (node (ref "HL4") (pin "A") (pinfunction "A_A") (pintype "passive"))
      (node (ref "R4") (pin "B2") (pinfunction "B2_B2") (pintype "passive"))
    )
    (net (code "28") (name "/N0G") (class "Default")
      (node (ref "HL10") (pin "A") (pinfunction "A_A") (pintype "passive"))
      (node (ref "R4") (pin "C2") (pinfunction "C2_C2") (pintype "passive"))
    )
    (net (code "29") (name "/N1A") (class "Default")
      (node (ref "HL2") (pin "A") (pinfunction "A_A") (pintype "passive"))
      (node (ref "R6") (pin "A2") (pinfunction "A2_A2") (pintype "passive"))
    )
    (net (code "30") (name "/N1B") (class "Default")
      (node (ref "HL8") (pin "A") (pinfunction "A_A") (pintype "passive"))
      (node (ref "R6") (pin "B2") (pinfunction "B2_B2") (pintype "passive"))
    )
    (net (code "31") (name "/N1C") (class "Default")
      (node (ref "HL17") (pin "A") (pinfunction "A_A") (pintype "passive"))
      (node (ref "R6") (pin "C2") (pinfunction "C2_C2") (pintype "passive"))
    )
    (net (code "32") (name "/N1D") (class "Default")
      (node (ref "HL20") (pin "A") (pinfunction "A_A") (pintype "passive"))
      (node (ref "R6") (pin "D2") (pinfunction "D2_D2") (pintype "passive"))
    )
    (net (code "33") (name "/N1E") (class "Default")
      (node (ref "HL14") (pin "A") (pinfunction "A_A") (pintype "passive"))
      (node (ref "R7") (pin "A2") (pinfunction "A2_A2") (pintype "passive"))
    )
    (net (code "34") (name "/N1F") (class "Default")
      (node (ref "HL5") (pin "A") (pinfunction "A_A") (pintype "passive"))
      (node (ref "R7") (pin "B2") (pinfunction "B2_B2") (pintype "passive"))
    )
    (net (code "35") (name "/N1G") (class "Default")
      (node (ref "HL11") (pin "A") (pinfunction "A_A") (pintype "passive"))
      (node (ref "R7") (pin "C2") (pinfunction "C2_C2") (pintype "passive"))
    )
    (net (code "36") (name "/N2A") (class "Default")
      (node (ref "HL3") (pin "A") (pinfunction "A_A") (pintype "passive"))
      (node (ref "R10") (pin "A2") (pinfunction "A2_A2") (pintype "passive"))
    )
    (net (code "37") (name "/N2B") (class "Default")
      (node (ref "HL9") (pin "A") (pinfunction "A_A") (pintype "passive"))
      (node (ref "R10") (pin "B2") (pinfunction "B2_B2") (pintype "passive"))
    )
    (net (code "38") (name "/N2C") (class "Default")
      (node (ref "HL18") (pin "A") (pinfunction "A_A") (pintype "passive"))
      (node (ref "R10") (pin "C2") (pinfunction "C2_C2") (pintype "passive"))
    )
    (net (code "39") (name "/N2D") (class "Default")
      (node (ref "HL21") (pin "A") (pinfunction "A_A") (pintype "passive"))
      (node (ref "R10") (pin "D2") (pinfunction "D2_D2") (pintype "passive"))
    )
    (net (code "40") (name "/N2E") (class "Default")
      (node (ref "HL15") (pin "A") (pinfunction "A_A") (pintype "passive"))
      (node (ref "R11") (pin "A2") (pinfunction "A2_A2") (pintype "passive"))
    )
    (net (code "41") (name "/N2F") (class "Default")
      (node (ref "HL6") (pin "A") (pinfunction "A_A") (pintype "passive"))
      (node (ref "R11") (pin "B2") (pinfunction "B2_B2") (pintype "passive"))
    )
    (net (code "42") (name "/N2G") (class "Default")
      (node (ref "HL12") (pin "A") (pinfunction "A_A") (pintype "passive"))
      (node (ref "R11") (pin "C2") (pinfunction "C2_C2") (pintype "passive"))
    )
    (net (code "43") (name "/P0_1") (class "Default")
      (node (ref "HL38") (pin "A") (pinfunction "A_A") (pintype "passive"))
      (node (ref "R5") (pin "2") (pinfunction "2_2") (pintype "passive"))
    )
    (net (code "44") (name "/P0_2") (class "Default")
      (node (ref "HL23") (pin "A") (pinfunction "A_A") (pintype "passive"))
      (node (ref "R35") (pin "2") (pinfunction "2_2") (pintype "passive"))
    )
    (net (code "45") (name "/P1") (class "Default")
      (node (ref "HL28") (pin "A") (pinfunction "A_A") (pintype "passive"))
      (node (ref "R14") (pin "2") (pinfunction "2_2") (pintype "passive"))
    )
    (net (code "46") (name "/P2_1") (class "Default")
      (node (ref "HL33") (pin "A") (pinfunction "A_A") (pintype "passive"))
      (node (ref "R37") (pin "2") (pinfunction "2_2") (pintype "passive"))
    )
    (net (code "47") (name "/P2_2") (class "Default")
      (node (ref "HL39") (pin "A") (pinfunction "A_A") (pintype "passive"))
      (node (ref "R38") (pin "2") (pinfunction "2_2") (pintype "passive"))
    )
    (net (code "48") (name "/P3") (class "Default")
      (node (ref "HL32") (pin "A") (pinfunction "A_A") (pintype "passive"))
      (node (ref "R36") (pin "2") (pinfunction "2_2") (pintype "passive"))
    )
    (net (code "49") (name "/P4") (class "Default")
      (node (ref "HL27") (pin "A") (pinfunction "A_A") (pintype "passive"))
      (node (ref "R18") (pin "2") (pinfunction "2_2") (pintype "passive"))
    )
    (net (code "50") (name "/P5") (class "Default")
      (node (ref "HL22") (pin "A") (pinfunction "A_A") (pintype "passive"))
      (node (ref "R19") (pin "2") (pinfunction "2_2") (pintype "passive"))
    )
    (net (code "51") (name "/PM2.5") (class "Default")
      (node (ref "A1") (pin "36") (pinfunction "IO22_36") (pintype "bidirectional"))
      (node (ref "R30") (pin "2") (pinfunction "2_2") (pintype "passive"))
      (node (ref "VD2") (pin "A") (pinfunction "A_A") (pintype "passive"))
    )
    (net (code "52") (name "/POWER_BTN") (class "Default")
      (node (ref "A1") (pin "4") (pinfunction "SENSOR_VP_4") (pintype "input"))
      (node (ref "PWR") (pin "1") (pinfunction "1_1") (pintype "passive"))
      (node (ref "R15") (pin "1") (pinfunction "1_1") (pintype "passive"))
    )
    (net (code "53") (name "/PW0") (class "Default")
      (node (ref "HL37") (pin "A") (pinfunction "A_A") (pintype "passive"))
      (node (ref "R4") (pin "D2") (pinfunction "D2_D2") (pintype "passive"))
    )
    (net (code "54") (name "/PW1") (class "Default")
      (node (ref "HL36") (pin "A") (pinfunction "A_A") (pintype "passive"))
      (node (ref "R7") (pin "D2") (pinfunction "D2_D2") (pintype "passive"))
    )
    (net (code "55") (name "/PW2") (class "Default")
      (node (ref "HL35") (pin "A") (pinfunction "A_A") (pintype "passive"))
      (node (ref "R11") (pin "D2") (pinfunction "D2_D2") (pintype "passive"))
    )
    (net (code "56") (name "/PW3") (class "Default")
      (node (ref "HL34") (pin "A") (pinfunction "A_A") (pintype "passive"))
      (node (ref "R20") (pin "2") (pinfunction "2_2") (pintype "passive"))
    )
    (net (code "57") (name "/RGB_ESP") (class "Default")
      (node (ref "A1") (pin "16") (pinfunction "IO13_16") (pintype "bidirectional"))
      (node (ref "DA2") (pin "3") (pinfunction "A_3") (pintype "passive"))
    )
    (net (code "58") (name "/RGB_LEDS") (class "Default")
      (node (ref "HL24") (pin "I") (pinfunction "DI_I") (pintype "passive"))
      (node (ref "HL25") (pin "I") (pinfunction "DI_I") (pintype "passive"))
      (node (ref "HL26") (pin "I") (pinfunction "DI_I") (pintype "passive"))
      (node (ref "HL29") (pin "I") (pinfunction "DI_I") (pintype "passive"))
      (node (ref "HL30") (pin "I") (pinfunction "DI_I") (pintype "passive"))
      (node (ref "HL31") (pin "I") (pinfunction "DI_I") (pintype "passive"))
      (node (ref "HL40") (pin "I") (pinfunction "DI_I") (pintype "passive"))
      (node (ref "HL41") (pin "I") (pinfunction "DI_I") (pintype "passive"))
      (node (ref "HL42") (pin "I") (pinfunction "DI_I") (pintype "passive"))
      (node (ref "HL43") (pin "I") (pinfunction "DI_I") (pintype "passive"))
      (node (ref "HL44") (pin "I") (pinfunction "DI_I") (pintype "passive"))
      (node (ref "R39") (pin "2") (pinfunction "2_2") (pintype "passive"))
    )
    (net (code "59") (name "/RGB_SW") (class "Default")
      (node (ref "A1") (pin "23") (pinfunction "IO15_23") (pintype "bidirectional"))
      (node (ref "DA2") (pin "5") (pinfunction "OE_5") (pintype "passive"))
    )
    (net (code "60") (name "/RTC_SCL") (class "Default")
      (node (ref "A1") (pin "33") (pinfunction "IO21_33") (pintype "bidirectional"))
      (node (ref "DD5") (pin "5") (pinfunction "SDA_5") (pintype "bidirectional"))
      (node (ref "R28") (pin "1") (pinfunction "1_1") (pintype "passive"))
    )
    (net (code "61") (name "/RTC_SDA") (class "Default")
      (node (ref "A1") (pin "31") (pinfunction "IO19_31") (pintype "bidirectional"))
      (node (ref "DD5") (pin "6") (pinfunction "SCL_6") (pintype "input"))
      (node (ref "R27") (pin "1") (pinfunction "1_1") (pintype "passive"))
    )
    (net (code "62") (name "/RX0") (class "Default")
      (node (ref "A1") (pin "34") (pinfunction "RXD0_34") (pintype "bidirectional"))
    )
    (net (code "63") (name "/TX0") (class "Default")
      (node (ref "A1") (pin "35") (pinfunction "TXD0_35") (pintype "bidirectional"))
    )
    (net (code "64") (name "/UP") (class "Default")
      (node (ref "LED_TOP") (pin "2") (pinfunction "2_2") (pintype "passive"))
      (node (ref "VT3") (pin "Y") (pinfunction "D_Y") (pintype "passive"))
    )
    (net (code "65") (name "/UV_BTN") (class "Default")
      (node (ref "A1") (pin "5") (pinfunction "SENSOR_VN_5") (pintype "input"))
      (node (ref "BUTTONS") (pin "1") (pinfunction "1_1") (pintype "passive"))
      (node (ref "R21") (pin "1") (pinfunction "1_1") (pintype "passive"))
    )
    (net (code "66") (name "/YY_LOGO") (class "Default")
      (node (ref "HL29") (pin "O") (pinfunction "DO_O") (pintype "passive"))
      (node (ref "LED_TOP") (pin "3") (pinfunction "3_3") (pintype "passive"))
    )
    (net (code "67") (name "3.3V") (class "Default")
      (node (ref "A1") (pin "2") (pinfunction "3V3_2") (pintype "power_in"))
      (node (ref "C2") (pin "2") (pinfunction "2_2") (pintype "passive"))
      (node (ref "C3") (pin "2") (pinfunction "2_2") (pintype "passive"))
      (node (ref "DA1") (pin "Y") (pinfunction "OUT_Y") (pintype "passive"))
      (node (ref "DA2") (pin "1") (pinfunction "VCCA_1") (pintype "passive"))
      (node (ref "R15") (pin "2") (pinfunction "2_2") (pintype "passive"))
      (node (ref "R21") (pin "2") (pinfunction "2_2") (pintype "passive"))
      (node (ref "R22") (pin "2") (pinfunction "2_2") (pintype "passive"))
      (node (ref "R23") (pin "2") (pinfunction "2_2") (pintype "passive"))
      (node (ref "R26") (pin "2") (pinfunction "2_2") (pintype "passive"))
      (node (ref "R27") (pin "2") (pinfunction "2_2") (pintype "passive"))
      (node (ref "R28") (pin "2") (pinfunction "2_2") (pintype "passive"))
      (node (ref "R3") (pin "2") (pinfunction "2_2") (pintype "passive"))
      (node (ref "R34") (pin "2") (pinfunction "2_2") (pintype "passive"))
      (node (ref "VD2") (pin "C") (pinfunction "C_C") (pintype "passive"))
    )
    (net (code "68") (name "GND") (class "Default")
      (node (ref "A1") (pin "1") (pinfunction "GND_1") (pintype "power_in"))
      (node (ref "A1") (pin "15") (pinfunction "GND_15") (pintype "power_in"))
      (node (ref "A1") (pin "38") (pinfunction "GND_38") (pintype "power_in"))
      (node (ref "BUTTONS") (pin "4") (pinfunction "4_4") (pintype "passive"))
      (node (ref "C1") (pin "1") (pinfunction "1_1") (pintype "passive"))
      (node (ref "C10") (pin "-") (pinfunction "-_-") (pintype "passive"))
      (node (ref "C11") (pin "1") (pinfunction "1_1") (pintype "passive"))
      (node (ref "C12") (pin "1") (pinfunction "1_1") (pintype "passive"))
      (node (ref "C13") (pin "1") (pinfunction "1_1") (pintype "passive"))
      (node (ref "C2") (pin "1") (pinfunction "1_1") (pintype "passive"))
      (node (ref "C3") (pin "1") (pinfunction "1_1") (pintype "passive"))
      (node (ref "C4") (pin "1") (pinfunction "1_1") (pintype "passive"))
      (node (ref "C5") (pin "1") (pinfunction "1_1") (pintype "passive"))
      (node (ref "C6") (pin "2") (pinfunction "2_2") (pintype "passive"))
      (node (ref "C7") (pin "1") (pinfunction "1_1") (pintype "passive"))
      (node (ref "C8") (pin "1") (pinfunction "1_1") (pintype "passive"))
      (node (ref "C9") (pin "2") (pinfunction "2_2") (pintype "passive"))
      (node (ref "DA1") (pin "X") (pinfunction "GND_X") (pintype "passive"))
      (node (ref "DA2") (pin "2") (pinfunction "GND_2") (pintype "passive"))
      (node (ref "DA3") (pin "2") (pinfunction "GND_2") (pintype "passive"))
      (node (ref "DD1") (pin "13") (pinfunction "~{OE}_13") (pintype "input"))
      (node (ref "DD1") (pin "8") (pinfunction "GND_8") (pintype "power_in"))
      (node (ref "DD2") (pin "13") (pinfunction "~{OE}_13") (pintype "input"))
      (node (ref "DD2") (pin "8") (pinfunction "GND_8") (pintype "power_in"))
      (node (ref "DD3") (pin "13") (pinfunction "~{OE}_13") (pintype "input"))
      (node (ref "DD3") (pin "8") (pinfunction "GND_8") (pintype "power_in"))
      (node (ref "DD4") (pin "13") (pinfunction "~{OE}_13") (pintype "input"))
      (node (ref "DD4") (pin "8") (pinfunction "GND_8") (pintype "power_in"))
      (node (ref "DD5") (pin "4") (pinfunction "VSS_4") (pintype "power_in"))
      (node (ref "DOOR") (pin "2") (pinfunction "2_2") (pintype "passive"))
      (node (ref "HL1") (pin "C") (pinfunction "C_C") (pintype "passive"))
      (node (ref "HL10") (pin "C") (pinfunction "C_C") (pintype "passive"))
      (node (ref "HL11") (pin "C") (pinfunction "C_C") (pintype "passive"))
      (node (ref "HL12") (pin "C") (pinfunction "C_C") (pintype "passive"))
      (node (ref "HL13") (pin "C") (pinfunction "C_C") (pintype "passive"))
      (node (ref "HL14") (pin "C") (pinfunction "C_C") (pintype "passive"))
      (node (ref "HL15") (pin "C") (pinfunction "C_C") (pintype "passive"))
      (node (ref "HL16") (pin "C") (pinfunction "C_C") (pintype "passive"))
      (node (ref "HL17") (pin "C") (pinfunction "C_C") (pintype "passive"))
      (node (ref "HL18") (pin "C") (pinfunction "C_C") (pintype "passive"))
      (node (ref "HL19") (pin "C") (pinfunction "C_C") (pintype "passive"))
      (node (ref "HL2") (pin "C") (pinfunction "C_C") (pintype "passive"))
      (node (ref "HL20") (pin "C") (pinfunction "C_C") (pintype "passive"))
      (node (ref "HL21") (pin "C") (pinfunction "C_C") (pintype "passive"))
      (node (ref "HL22") (pin "C") (pinfunction "C_C") (pintype "passive"))
      (node (ref "HL23") (pin "C") (pinfunction "C_C") (pintype "passive"))
      (node (ref "HL24") (pin "-") (pinfunction "GND_-") (pintype "passive"))
      (node (ref "HL25") (pin "-") (pinfunction "GND_-") (pintype "passive"))
      (node (ref "HL26") (pin "-") (pinfunction "GND_-") (pintype "passive"))
      (node (ref "HL27") (pin "C") (pinfunction "C_C") (pintype "passive"))
      (node (ref "HL28") (pin "C") (pinfunction "C_C") (pintype "passive"))
      (node (ref "HL29") (pin "-") (pinfunction "GND_-") (pintype "passive"))
      (node (ref "HL3") (pin "C") (pinfunction "C_C") (pintype "passive"))
      (node (ref "HL30") (pin "-") (pinfunction "GND_-") (pintype "passive"))
      (node (ref "HL31") (pin "-") (pinfunction "GND_-") (pintype "passive"))
      (node (ref "HL32") (pin "C") (pinfunction "C_C") (pintype "passive"))
      (node (ref "HL33") (pin "C") (pinfunction "C_C") (pintype "passive"))
      (node (ref "HL34") (pin "C") (pinfunction "C_C") (pintype "passive"))
      (node (ref "HL35") (pin "C") (pinfunction "C_C") (pintype "passive"))
      (node (ref "HL36") (pin "C") (pinfunction "C_C") (pintype "passive"))
      (node (ref "HL37") (pin "C") (pinfunction "C_C") (pintype "passive"))
      (node (ref "HL38") (pin "C") (pinfunction "C_C") (pintype "passive"))
      (node (ref "HL39") (pin "C") (pinfunction "C_C") (pintype "passive"))
      (node (ref "HL4") (pin "C") (pinfunction "C_C") (pintype "passive"))
      (node (ref "HL40") (pin "-") (pinfunction "GND_-") (pintype "passive"))
      (node (ref "HL41") (pin "-") (pinfunction "GND_-") (pintype "passive"))
      (node (ref "HL42") (pin "-") (pinfunction "GND_-") (pintype "passive"))
      (node (ref "HL43") (pin "-") (pinfunction "GND_-") (pintype "passive"))
      (node (ref "HL44") (pin "-") (pinfunction "GND_-") (pintype "passive"))
      (node (ref "HL5") (pin "C") (pinfunction "C_C") (pintype "passive"))
      (node (ref "HL6") (pin "C") (pinfunction "C_C") (pintype "passive"))
      (node (ref "HL7") (pin "C") (pinfunction "C_C") (pintype "passive"))
      (node (ref "HL8") (pin "C") (pinfunction "C_C") (pintype "passive"))
      (node (ref "HL9") (pin "C") (pinfunction "C_C") (pintype "passive"))
      (node (ref "PM2.5") (pin "5") (pinfunction "5_5") (pintype "passive"))
      (node (ref "POWER") (pin "5") (pinfunction "5_5") (pintype "passive"))
      (node (ref "POWER") (pin "6") (pinfunction "6_6") (pintype "passive"))
      (node (ref "PWR") (pin "2") (pinfunction "2_2") (pintype "passive"))
      (node (ref "R17") (pin "1") (pinfunction "1_1") (pintype "passive"))
      (node (ref "R25") (pin "1") (pinfunction "1_1") (pintype "passive"))
      (node (ref "R32") (pin "1") (pinfunction "1_1") (pintype "passive"))
      (node (ref "R40") (pin "1") (pinfunction "1_1") (pintype "passive"))
      (node (ref "R9") (pin "1") (pinfunction "1_1") (pintype "passive"))
      (node (ref "VT1") (pin "Z") (pinfunction "S_Z") (pintype "passive"))
      (node (ref "VT3") (pin "Z") (pinfunction "S_Z") (pintype "passive"))
      (node (ref "VT4") (pin "Z") (pinfunction "S_Z") (pintype "passive"))
      (node (ref "VT5") (pin "Z") (pinfunction "S_Z") (pintype "passive"))
    )
    (net (code "69") (name "Net-(C10-Pad+)") (class "Default")
      (node (ref "C10") (pin "+") (pinfunction "+_+") (pintype "passive"))
      (node (ref "R29") (pin "2") (pinfunction "2_2") (pintype "passive"))
    )
    (net (code "70") (name "Net-(DA2-B)") (class "Default")
      (node (ref "DA2") (pin "4") (pinfunction "B_4") (pintype "passive"))
      (node (ref "R39") (pin "1") (pinfunction "1_1") (pintype "passive"))
    )
    (net (code "71") (name "Net-(DA3-FB)") (class "Default")
      (node (ref "DA3") (pin "3") (pinfunction "FB_3") (pintype "input"))
      (node (ref "R41") (pin "1") (pinfunction "1_1") (pintype "passive"))
      (node (ref "VD4") (pin "A") (pinfunction "A_A") (pintype "passive"))
    )
    (net (code "72") (name "Net-(DA3-SW)") (class "Default")
      (node (ref "DA3") (pin "1") (pinfunction "SW_1") (pintype "output"))
      (node (ref "L1") (pin "2") (pinfunction "2_2") (pintype "passive"))
      (node (ref "VD3") (pin "A") (pinfunction "A_A") (pintype "passive"))
    )
    (net (code "73") (name "Net-(DD1-Q0)") (class "Default")
      (node (ref "DD1") (pin "15") (pinfunction "Q0_15") (pintype "output"))
      (node (ref "R2") (pin "A1") (pinfunction "A1_A1") (pintype "passive"))
    )
    (net (code "74") (name "Net-(DD1-Q1)") (class "Default")
      (node (ref "DD1") (pin "1") (pinfunction "Q1_1") (pintype "output"))
      (node (ref "R2") (pin "B1") (pinfunction "B1_B1") (pintype "passive"))
    )
    (net (code "75") (name "Net-(DD1-Q2)") (class "Default")
      (node (ref "DD1") (pin "2") (pinfunction "Q2_2") (pintype "output"))
      (node (ref "R2") (pin "C1") (pinfunction "C1_C1") (pintype "passive"))
    )
    (net (code "76") (name "Net-(DD1-Q3)") (class "Default")
      (node (ref "DD1") (pin "3") (pinfunction "Q3_3") (pintype "output"))
      (node (ref "R2") (pin "D1") (pinfunction "D1_D1") (pintype "passive"))
    )
    (net (code "77") (name "Net-(DD1-Q4)") (class "Default")
      (node (ref "DD1") (pin "4") (pinfunction "Q4_4") (pintype "output"))
      (node (ref "R4") (pin "A1") (pinfunction "A1_A1") (pintype "passive"))
    )
    (net (code "78") (name "Net-(DD1-Q5)") (class "Default")
      (node (ref "DD1") (pin "5") (pinfunction "Q5_5") (pintype "output"))
      (node (ref "R4") (pin "B1") (pinfunction "B1_B1") (pintype "passive"))
    )
    (net (code "79") (name "Net-(DD1-Q6)") (class "Default")
      (node (ref "DD1") (pin "6") (pinfunction "Q6_6") (pintype "output"))
      (node (ref "R4") (pin "C1") (pinfunction "C1_C1") (pintype "passive"))
    )
    (net (code "80") (name "Net-(DD1-Q7)") (class "Default")
      (node (ref "DD1") (pin "7") (pinfunction "Q7_7") (pintype "output"))
      (node (ref "R4") (pin "D1") (pinfunction "D1_D1") (pintype "passive"))
    )
    (net (code "81") (name "Net-(DD1-Q7S)") (class "Default")
      (node (ref "DD1") (pin "9") (pinfunction "Q7S_9") (pintype "output"))
      (node (ref "DD2") (pin "14") (pinfunction "DS_14") (pintype "input"))
    )
    (net (code "82") (name "Net-(DD1-~{MR})") (class "Default")
      (node (ref "C7") (pin "2") (pinfunction "2_2") (pintype "passive"))
      (node (ref "DD1") (pin "10") (pinfunction "~{MR}_10") (pintype "input"))
      (node (ref "DD2") (pin "10") (pinfunction "~{MR}_10") (pintype "input"))
      (node (ref "DD3") (pin "10") (pinfunction "~{MR}_10") (pintype "input"))
      (node (ref "DD4") (pin "10") (pinfunction "~{MR}_10") (pintype "input"))
      (node (ref "R1") (pin "1") (pinfunction "1_1") (pintype "passive"))
    )
    (net (code "83") (name "Net-(DD2-Q0)") (class "Default")
      (node (ref "DD2") (pin "15") (pinfunction "Q0_15") (pintype "output"))
      (node (ref "R6") (pin "A1") (pinfunction "A1_A1") (pintype "passive"))
    )
    (net (code "84") (name "Net-(DD2-Q1)") (class "Default")
      (node (ref "DD2") (pin "1") (pinfunction "Q1_1") (pintype "output"))
      (node (ref "R6") (pin "B1") (pinfunction "B1_B1") (pintype "passive"))
    )
    (net (code "85") (name "Net-(DD2-Q2)") (class "Default")
      (node (ref "DD2") (pin "2") (pinfunction "Q2_2") (pintype "output"))
      (node (ref "R6") (pin "C1") (pinfunction "C1_C1") (pintype "passive"))
    )
    (net (code "86") (name "Net-(DD2-Q3)") (class "Default")
      (node (ref "DD2") (pin "3") (pinfunction "Q3_3") (pintype "output"))
      (node (ref "R6") (pin "D1") (pinfunction "D1_D1") (pintype "passive"))
    )
    (net (code "87") (name "Net-(DD2-Q4)") (class "Default")
      (node (ref "DD2") (pin "4") (pinfunction "Q4_4") (pintype "output"))
      (node (ref "R7") (pin "A1") (pinfunction "A1_A1") (pintype "passive"))
    )
    (net (code "88") (name "Net-(DD2-Q5)") (class "Default")
      (node (ref "DD2") (pin "5") (pinfunction "Q5_5") (pintype "output"))
      (node (ref "R7") (pin "B1") (pinfunction "B1_B1") (pintype "passive"))
    )
    (net (code "89") (name "Net-(DD2-Q6)") (class "Default")
      (node (ref "DD2") (pin "6") (pinfunction "Q6_6") (pintype "output"))
      (node (ref "R7") (pin "C1") (pinfunction "C1_C1") (pintype "passive"))
    )
    (net (code "90") (name "Net-(DD2-Q7)") (class "Default")
      (node (ref "DD2") (pin "7") (pinfunction "Q7_7") (pintype "output"))
      (node (ref "R7") (pin "D1") (pinfunction "D1_D1") (pintype "passive"))
    )
    (net (code "91") (name "Net-(DD2-Q7S)") (class "Default")
      (node (ref "DD2") (pin "9") (pinfunction "Q7S_9") (pintype "output"))
      (node (ref "DD3") (pin "14") (pinfunction "DS_14") (pintype "input"))
    )
    (net (code "92") (name "Net-(DD3-Q0)") (class "Default")
      (node (ref "DD3") (pin "15") (pinfunction "Q0_15") (pintype "output"))
      (node (ref "R10") (pin "A1") (pinfunction "A1_A1") (pintype "passive"))
    )
    (net (code "93") (name "Net-(DD3-Q1)") (class "Default")
      (node (ref "DD3") (pin "1") (pinfunction "Q1_1") (pintype "output"))
      (node (ref "R10") (pin "B1") (pinfunction "B1_B1") (pintype "passive"))
    )
    (net (code "94") (name "Net-(DD3-Q2)") (class "Default")
      (node (ref "DD3") (pin "2") (pinfunction "Q2_2") (pintype "output"))
      (node (ref "R10") (pin "C1") (pinfunction "C1_C1") (pintype "passive"))
    )
    (net (code "95") (name "Net-(DD3-Q3)") (class "Default")
      (node (ref "DD3") (pin "3") (pinfunction "Q3_3") (pintype "output"))
      (node (ref "R10") (pin "D1") (pinfunction "D1_D1") (pintype "passive"))
    )
    (net (code "96") (name "Net-(DD3-Q4)") (class "Default")
      (node (ref "DD3") (pin "4") (pinfunction "Q4_4") (pintype "output"))
      (node (ref "R11") (pin "A1") (pinfunction "A1_A1") (pintype "passive"))
    )
    (net (code "97") (name "Net-(DD3-Q5)") (class "Default")
      (node (ref "DD3") (pin "5") (pinfunction "Q5_5") (pintype "output"))
      (node (ref "R11") (pin "B1") (pinfunction "B1_B1") (pintype "passive"))
    )
    (net (code "98") (name "Net-(DD3-Q6)") (class "Default")
      (node (ref "DD3") (pin "6") (pinfunction "Q6_6") (pintype "output"))
      (node (ref "R11") (pin "C1") (pinfunction "C1_C1") (pintype "passive"))
    )
    (net (code "99") (name "Net-(DD3-Q7)") (class "Default")
      (node (ref "DD3") (pin "7") (pinfunction "Q7_7") (pintype "output"))
      (node (ref "R11") (pin "D1") (pinfunction "D1_D1") (pintype "passive"))
    )
    (net (code "100") (name "Net-(DD3-Q7S)") (class "Default")
      (node (ref "DD3") (pin "9") (pinfunction "Q7S_9") (pintype "output"))
      (node (ref "DD4") (pin "14") (pinfunction "DS_14") (pintype "input"))
    )
    (net (code "101") (name "Net-(DD4-Q1)") (class "Default")
      (node (ref "DD4") (pin "1") (pinfunction "Q1_1") (pintype "output"))
      (node (ref "R35") (pin "1") (pinfunction "1_1") (pintype "passive"))
      (node (ref "R5") (pin "1") (pinfunction "1_1") (pintype "passive"))
    )
    (net (code "102") (name "Net-(DD4-Q2)") (class "Default")
      (node (ref "DD4") (pin "2") (pinfunction "Q2_2") (pintype "output"))
      (node (ref "R14") (pin "1") (pinfunction "1_1") (pintype "passive"))
    )
    (net (code "103") (name "Net-(DD4-Q3)") (class "Default")
      (node (ref "DD4") (pin "3") (pinfunction "Q3_3") (pintype "output"))
      (node (ref "R37") (pin "1") (pinfunction "1_1") (pintype "passive"))
      (node (ref "R38") (pin "1") (pinfunction "1_1") (pintype "passive"))
    )
    (net (code "104") (name "Net-(DD4-Q4)") (class "Default")
      (node (ref "DD4") (pin "4") (pinfunction "Q4_4") (pintype "output"))
      (node (ref "R36") (pin "1") (pinfunction "1_1") (pintype "passive"))
    )
    (net (code "105") (name "Net-(DD4-Q5)") (class "Default")
      (node (ref "DD4") (pin "5") (pinfunction "Q5_5") (pintype "output"))
      (node (ref "R18") (pin "1") (pinfunction "1_1") (pintype "passive"))
    )
    (net (code "106") (name "Net-(DD4-Q6)") (class "Default")
      (node (ref "DD4") (pin "6") (pinfunction "Q6_6") (pintype "output"))
      (node (ref "R19") (pin "1") (pinfunction "1_1") (pintype "passive"))
    )
    (net (code "107") (name "Net-(DD4-Q7)") (class "Default")
      (node (ref "DD4") (pin "7") (pinfunction "Q7_7") (pintype "output"))
      (node (ref "R20") (pin "1") (pinfunction "1_1") (pintype "passive"))
    )
    (net (code "108") (name "Net-(DD5-OSCI)") (class "Default")
      (node (ref "C8") (pin "2") (pinfunction "2_2") (pintype "passive"))
      (node (ref "DD5") (pin "1") (pinfunction "OSCI_1") (pintype "passive"))
      (node (ref "ZQ1") (pin "1") (pinfunction "1_1") (pintype "passive"))
    )
    (net (code "109") (name "Net-(DD5-OSCO)") (class "Default")
      (node (ref "C11") (pin "2") (pinfunction "2_2") (pintype "passive"))
      (node (ref "DD5") (pin "2") (pinfunction "OSCO_2") (pintype "passive"))
      (node (ref "ZQ1") (pin "2") (pinfunction "2_2") (pintype "passive"))
    )
    (net (code "110") (name "Net-(DD5-VDD)") (class "Default")
      (node (ref "C9") (pin "1") (pinfunction "1_1") (pintype "passive"))
      (node (ref "DD5") (pin "8") (pinfunction "VDD_8") (pintype "power_in"))
      (node (ref "R29") (pin "1") (pinfunction "1_1") (pintype "passive"))
      (node (ref "VD1") (pin "C") (pinfunction "C_C") (pintype "passive"))
    )
    (net (code "111") (name "Net-(LED_MID-Pad3)") (class "Default")
      (node (ref "LED_MID") (pin "3") (pinfunction "3_3") (pintype "passive"))
      (node (ref "LED_TOP") (pin "4") (pinfunction "4_4") (pintype "passive"))
    )
    (net (code "112") (name "Net-(LED_MID-Pad4)") (class "Default")
      (node (ref "LED_MID") (pin "4") (pinfunction "4_4") (pintype "passive"))
      (node (ref "L_DOWN") (pin "3") (pinfunction "3_3") (pintype "passive"))
    )
    (net (code "113") (name "Net-(PM2.5-Pad2)") (class "Default")
      (node (ref "PM2.5") (pin "2") (pinfunction "2_2") (pintype "passive"))
      (node (ref "R30") (pin "1") (pinfunction "1_1") (pintype "passive"))
    )
    (net (code "114") (name "Net-(POWER-Pad4)") (class "Default")
      (node (ref "POWER") (pin "4") (pinfunction "4_4") (pintype "passive"))
      (node (ref "R33") (pin "1") (pinfunction "1_1") (pintype "passive"))
    )
    (net (code "115") (name "Net-(VT1-G)") (class "Default")
      (node (ref "R8") (pin "2") (pinfunction "2_2") (pintype "passive"))
      (node (ref "R9") (pin "2") (pinfunction "2_2") (pintype "passive"))
      (node (ref "VT1") (pin "X") (pinfunction "G_X") (pintype "passive"))
    )
    (net (code "116") (name "Net-(VT3-G)") (class "Default")
      (node (ref "R16") (pin "2") (pinfunction "2_2") (pintype "passive"))
      (node (ref "R17") (pin "2") (pinfunction "2_2") (pintype "passive"))
      (node (ref "VT3") (pin "X") (pinfunction "G_X") (pintype "passive"))
    )
    (net (code "117") (name "Net-(VT4-G)") (class "Default")
      (node (ref "R24") (pin "2") (pinfunction "2_2") (pintype "passive"))
      (node (ref "R25") (pin "2") (pinfunction "2_2") (pintype "passive"))
      (node (ref "VT4") (pin "X") (pinfunction "G_X") (pintype "passive"))
    )
    (net (code "118") (name "Net-(VT5-G)") (class "Default")
      (node (ref "R31") (pin "2") (pinfunction "2_2") (pintype "passive"))
      (node (ref "R32") (pin "2") (pinfunction "2_2") (pintype "passive"))
      (node (ref "VT5") (pin "X") (pinfunction "G_X") (pintype "passive"))
    )
    (net (code "119") (name "unconnected-(A1-IO2-Pad24)") (class "Default")
      (node (ref "A1") (pin "24") (pinfunction "IO2_24") (pintype "bidirectional"))
    )
    (net (code "120") (name "unconnected-(A1-IO4-Pad26)") (class "Default")
      (node (ref "A1") (pin "26") (pinfunction "IO4_26") (pintype "bidirectional"))
    )
    (net (code "121") (name "unconnected-(A1-IO16-Pad27)") (class "Default")
      (node (ref "A1") (pin "27") (pinfunction "IO16_27") (pintype "bidirectional"))
    )
    (net (code "122") (name "unconnected-(A1-NC-Pad32)") (class "Default")
      (node (ref "A1") (pin "32") (pinfunction "NC_32") (pintype "bidirectional"))
    )
    (net (code "123") (name "unconnected-(A1-SCK{slash}CLK-Pad20)") (class "Default")
      (node (ref "A1") (pin "20") (pinfunction "SCK/CLK_20") (pintype "bidirectional"))
    )
    (net (code "124") (name "unconnected-(A1-SCS{slash}CMD-Pad19)") (class "Default")
      (node (ref "A1") (pin "19") (pinfunction "SCS/CMD_19") (pintype "bidirectional"))
    )
    (net (code "125") (name "unconnected-(A1-SDI{slash}SD1-Pad22)") (class "Default")
      (node (ref "A1") (pin "22") (pinfunction "SDI/SD1_22") (pintype "bidirectional"))
    )
    (net (code "126") (name "unconnected-(A1-SDO{slash}SD0-Pad21)") (class "Default")
      (node (ref "A1") (pin "21") (pinfunction "SDO/SD0_21") (pintype "bidirectional"))
    )
    (net (code "127") (name "unconnected-(A1-SHD{slash}SD2-Pad17)") (class "Default")
      (node (ref "A1") (pin "17") (pinfunction "SHD/SD2_17") (pintype "bidirectional"))
    )
    (net (code "128") (name "unconnected-(A1-SWP{slash}SD3-Pad18)") (class "Default")
      (node (ref "A1") (pin "18") (pinfunction "SWP/SD3_18") (pintype "bidirectional"))
    )
    (net (code "129") (name "unconnected-(DD4-Q0-Pad15)") (class "Default")
      (node (ref "DD4") (pin "15") (pinfunction "Q0_15") (pintype "output"))
    )
    (net (code "130") (name "unconnected-(DD4-Q7S-Pad9)") (class "Default")
      (node (ref "DD4") (pin "9") (pinfunction "Q7S_9") (pintype "output"))
    )
    (net (code "131") (name "unconnected-(DD5-CLKOUT-Pad7)") (class "Default")
      (node (ref "DD5") (pin "7") (pinfunction "CLKOUT_7") (pintype "output"))
    )
    (net (code "132") (name "unconnected-(DD5-~{INT}-Pad3)") (class "Default")
      (node (ref "DD5") (pin "3") (pinfunction "~{INT}_3") (pintype "output"))
    )
    (net (code "133") (name "unconnected-(HL24-DO-PadO)") (class "Default")
      (node (ref "HL24") (pin "O") (pinfunction "DO_O") (pintype "passive"))
    )
    (net (code "134") (name "unconnected-(HL25-DO-PadO)") (class "Default")
      (node (ref "HL25") (pin "O") (pinfunction "DO_O") (pintype "passive"))
    )
    (net (code "135") (name "unconnected-(HL26-DO-PadO)") (class "Default")
      (node (ref "HL26") (pin "O") (pinfunction "DO_O") (pintype "passive"))
    )
    (net (code "136") (name "unconnected-(HL30-DO-PadO)") (class "Default")
      (node (ref "HL30") (pin "O") (pinfunction "DO_O") (pintype "passive"))
    )
    (net (code "137") (name "unconnected-(HL31-DO-PadO)") (class "Default")
      (node (ref "HL31") (pin "O") (pinfunction "DO_O") (pintype "passive"))
    )
    (net (code "138") (name "unconnected-(HL40-DO-PadO)") (class "Default")
      (node (ref "HL40") (pin "O") (pinfunction "DO_O") (pintype "passive"))
    )
    (net (code "139") (name "unconnected-(HL41-DO-PadO)") (class "Default")
      (node (ref "HL41") (pin "O") (pinfunction "DO_O") (pintype "passive"))
    )
    (net (code "140") (name "unconnected-(HL42-DO-PadO)") (class "Default")
      (node (ref "HL42") (pin "O") (pinfunction "DO_O") (pintype "passive"))
    )
    (net (code "141") (name "unconnected-(HL43-DO-PadO)") (class "Default")
      (node (ref "HL43") (pin "O") (pinfunction "DO_O") (pintype "passive"))
    )
    (net (code "142") (name "unconnected-(HL44-DO-PadO)") (class "Default")
      (node (ref "HL44") (pin "O") (pinfunction "DO_O") (pintype "passive"))
    )
    (net (code "143") (name "unconnected-(PM2.5-Pad1)") (class "Default")
      (node (ref "PM2.5") (pin "1") (pinfunction "1_1") (pintype "passive"))
    )
    (net (code "144") (name "unconnected-(PM2.5-Pad4)") (class "Default")
      (node (ref "PM2.5") (pin "4") (pinfunction "4_4") (pintype "passive"))
    )
  )
)
